# logmega.net
KiCad netlist of a schematic drawn in EAGLE
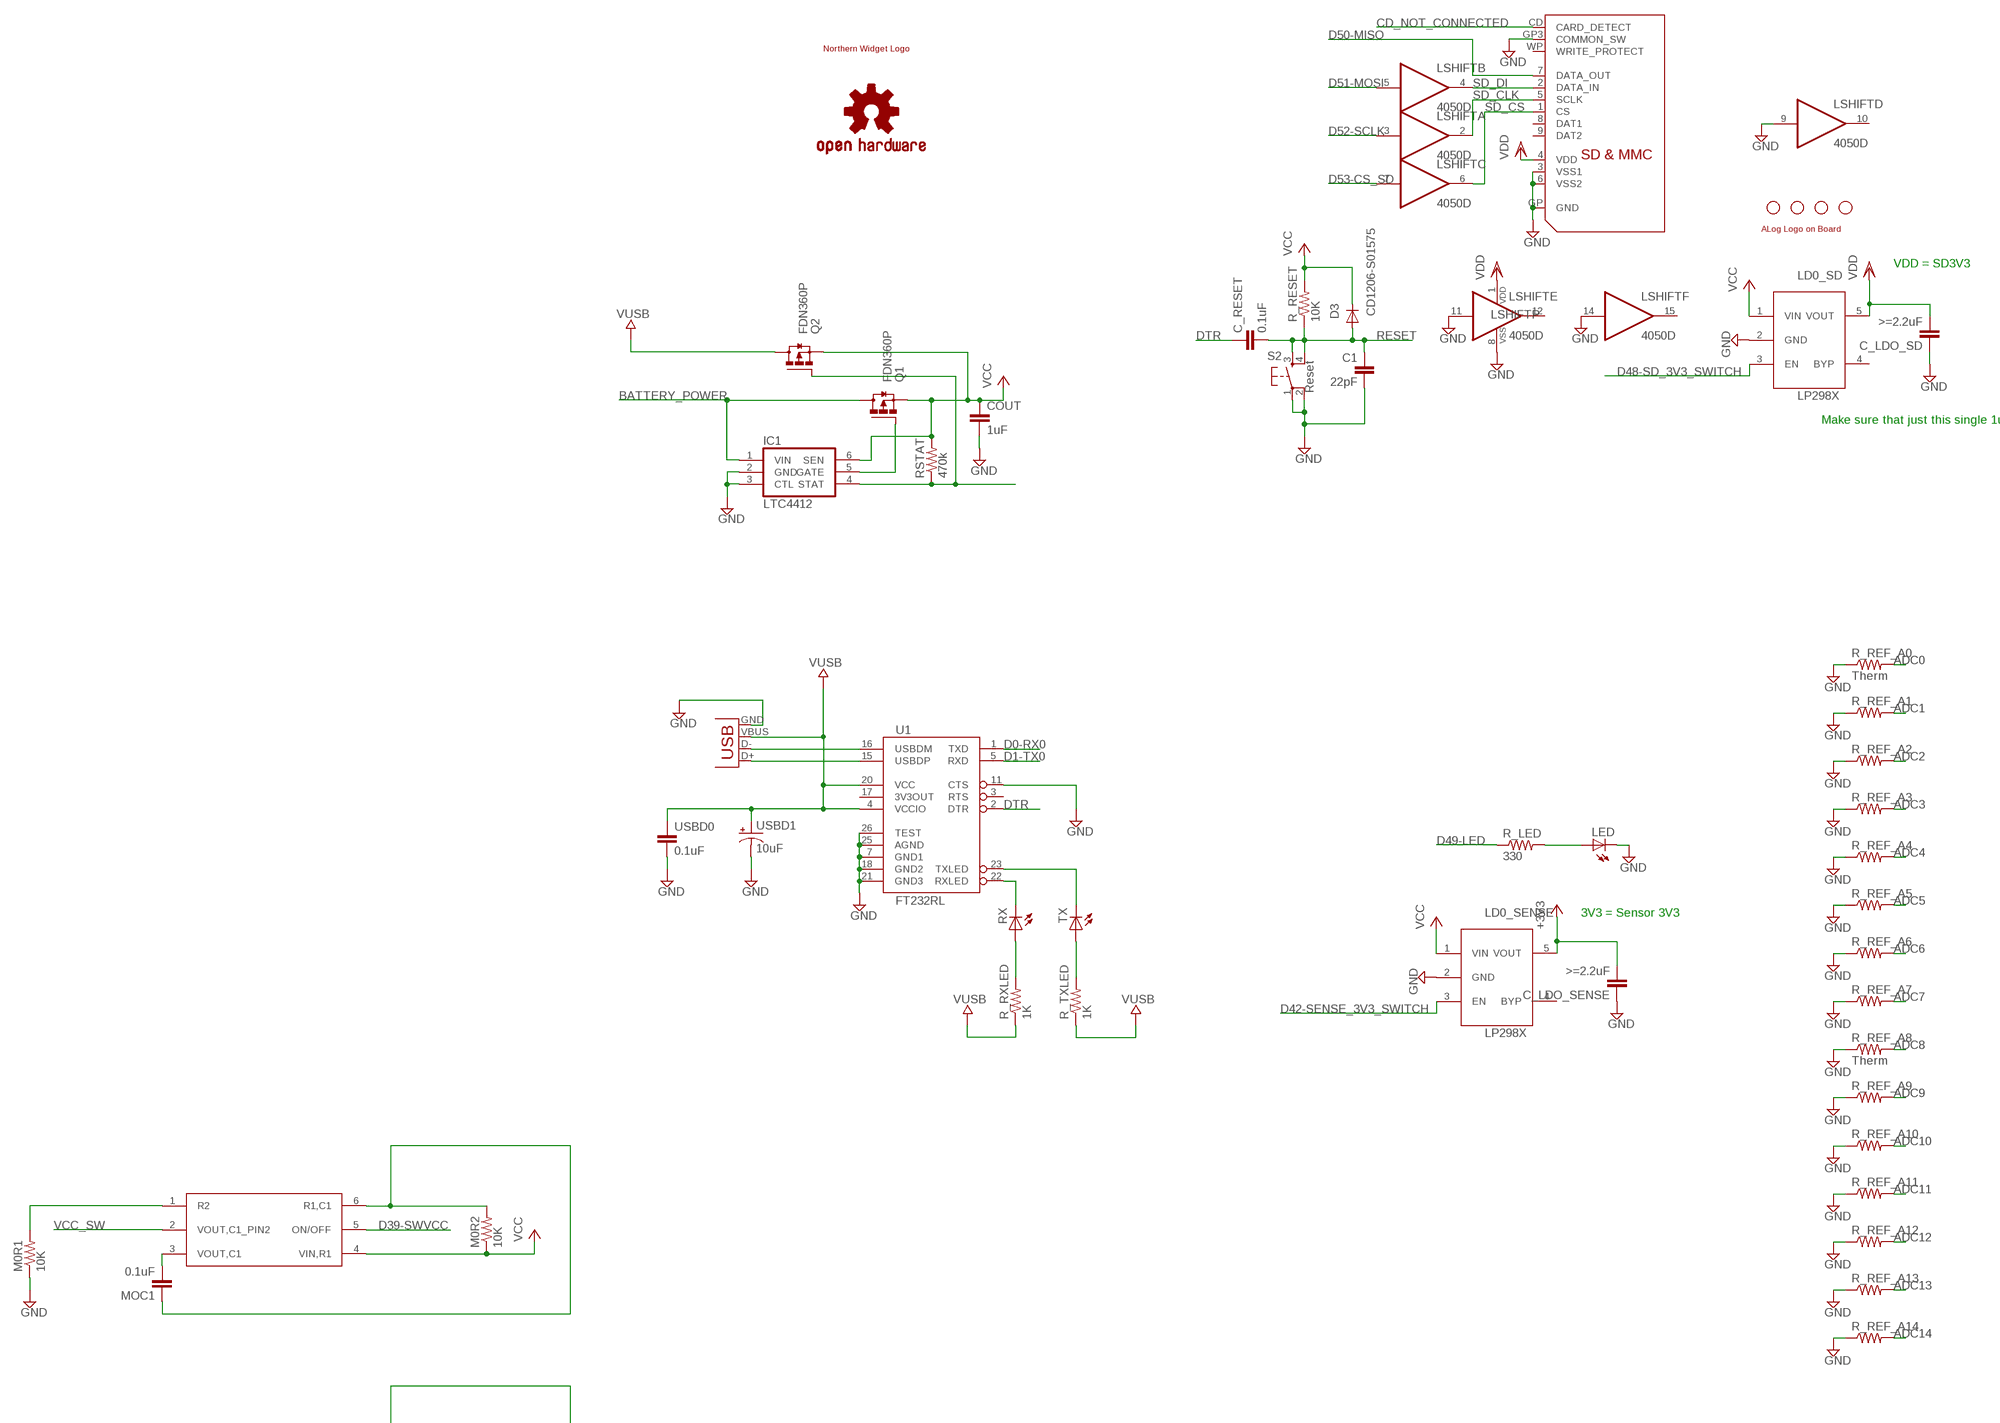
[diagram p0: schematic, sheet 1, part 1 of 3]
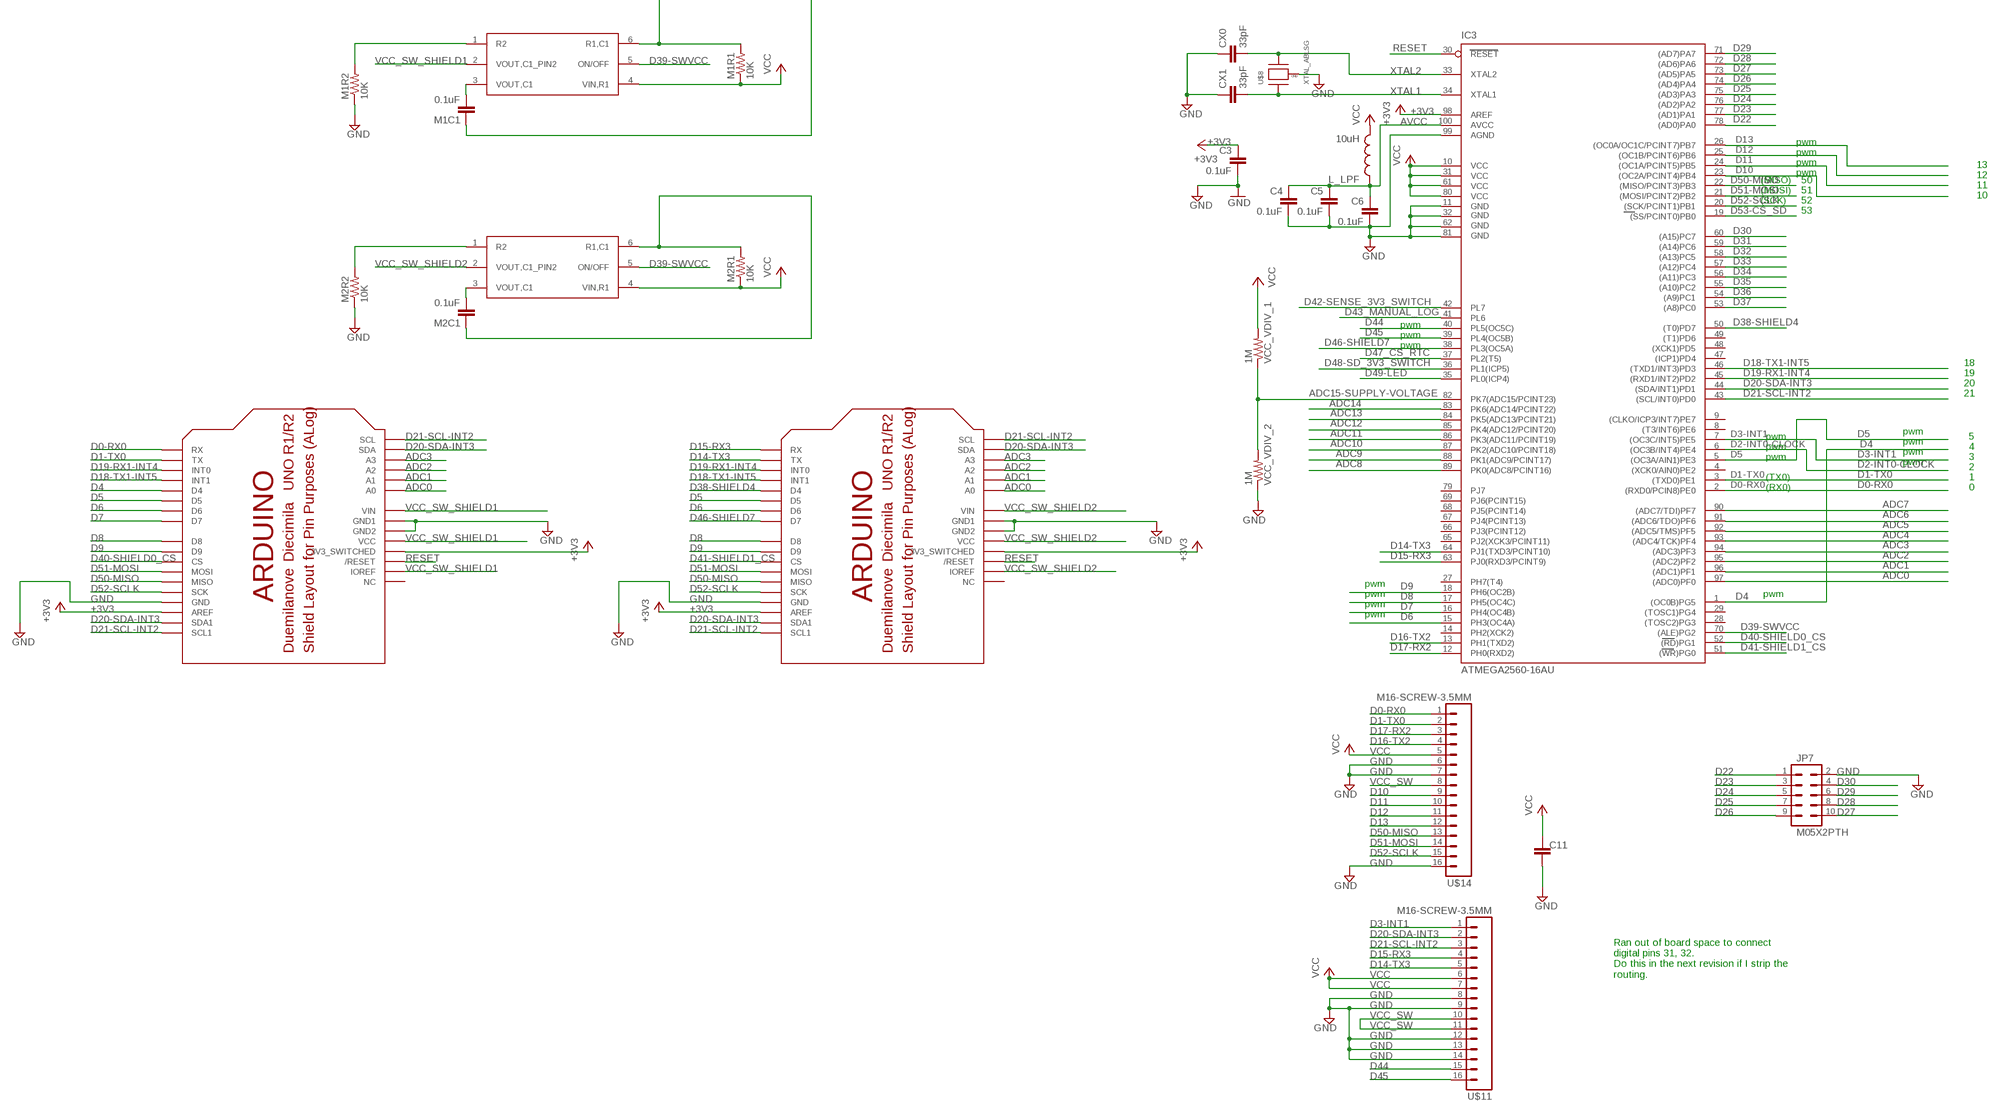
[diagram p1: schematic, sheet 1, part 2 of 3]
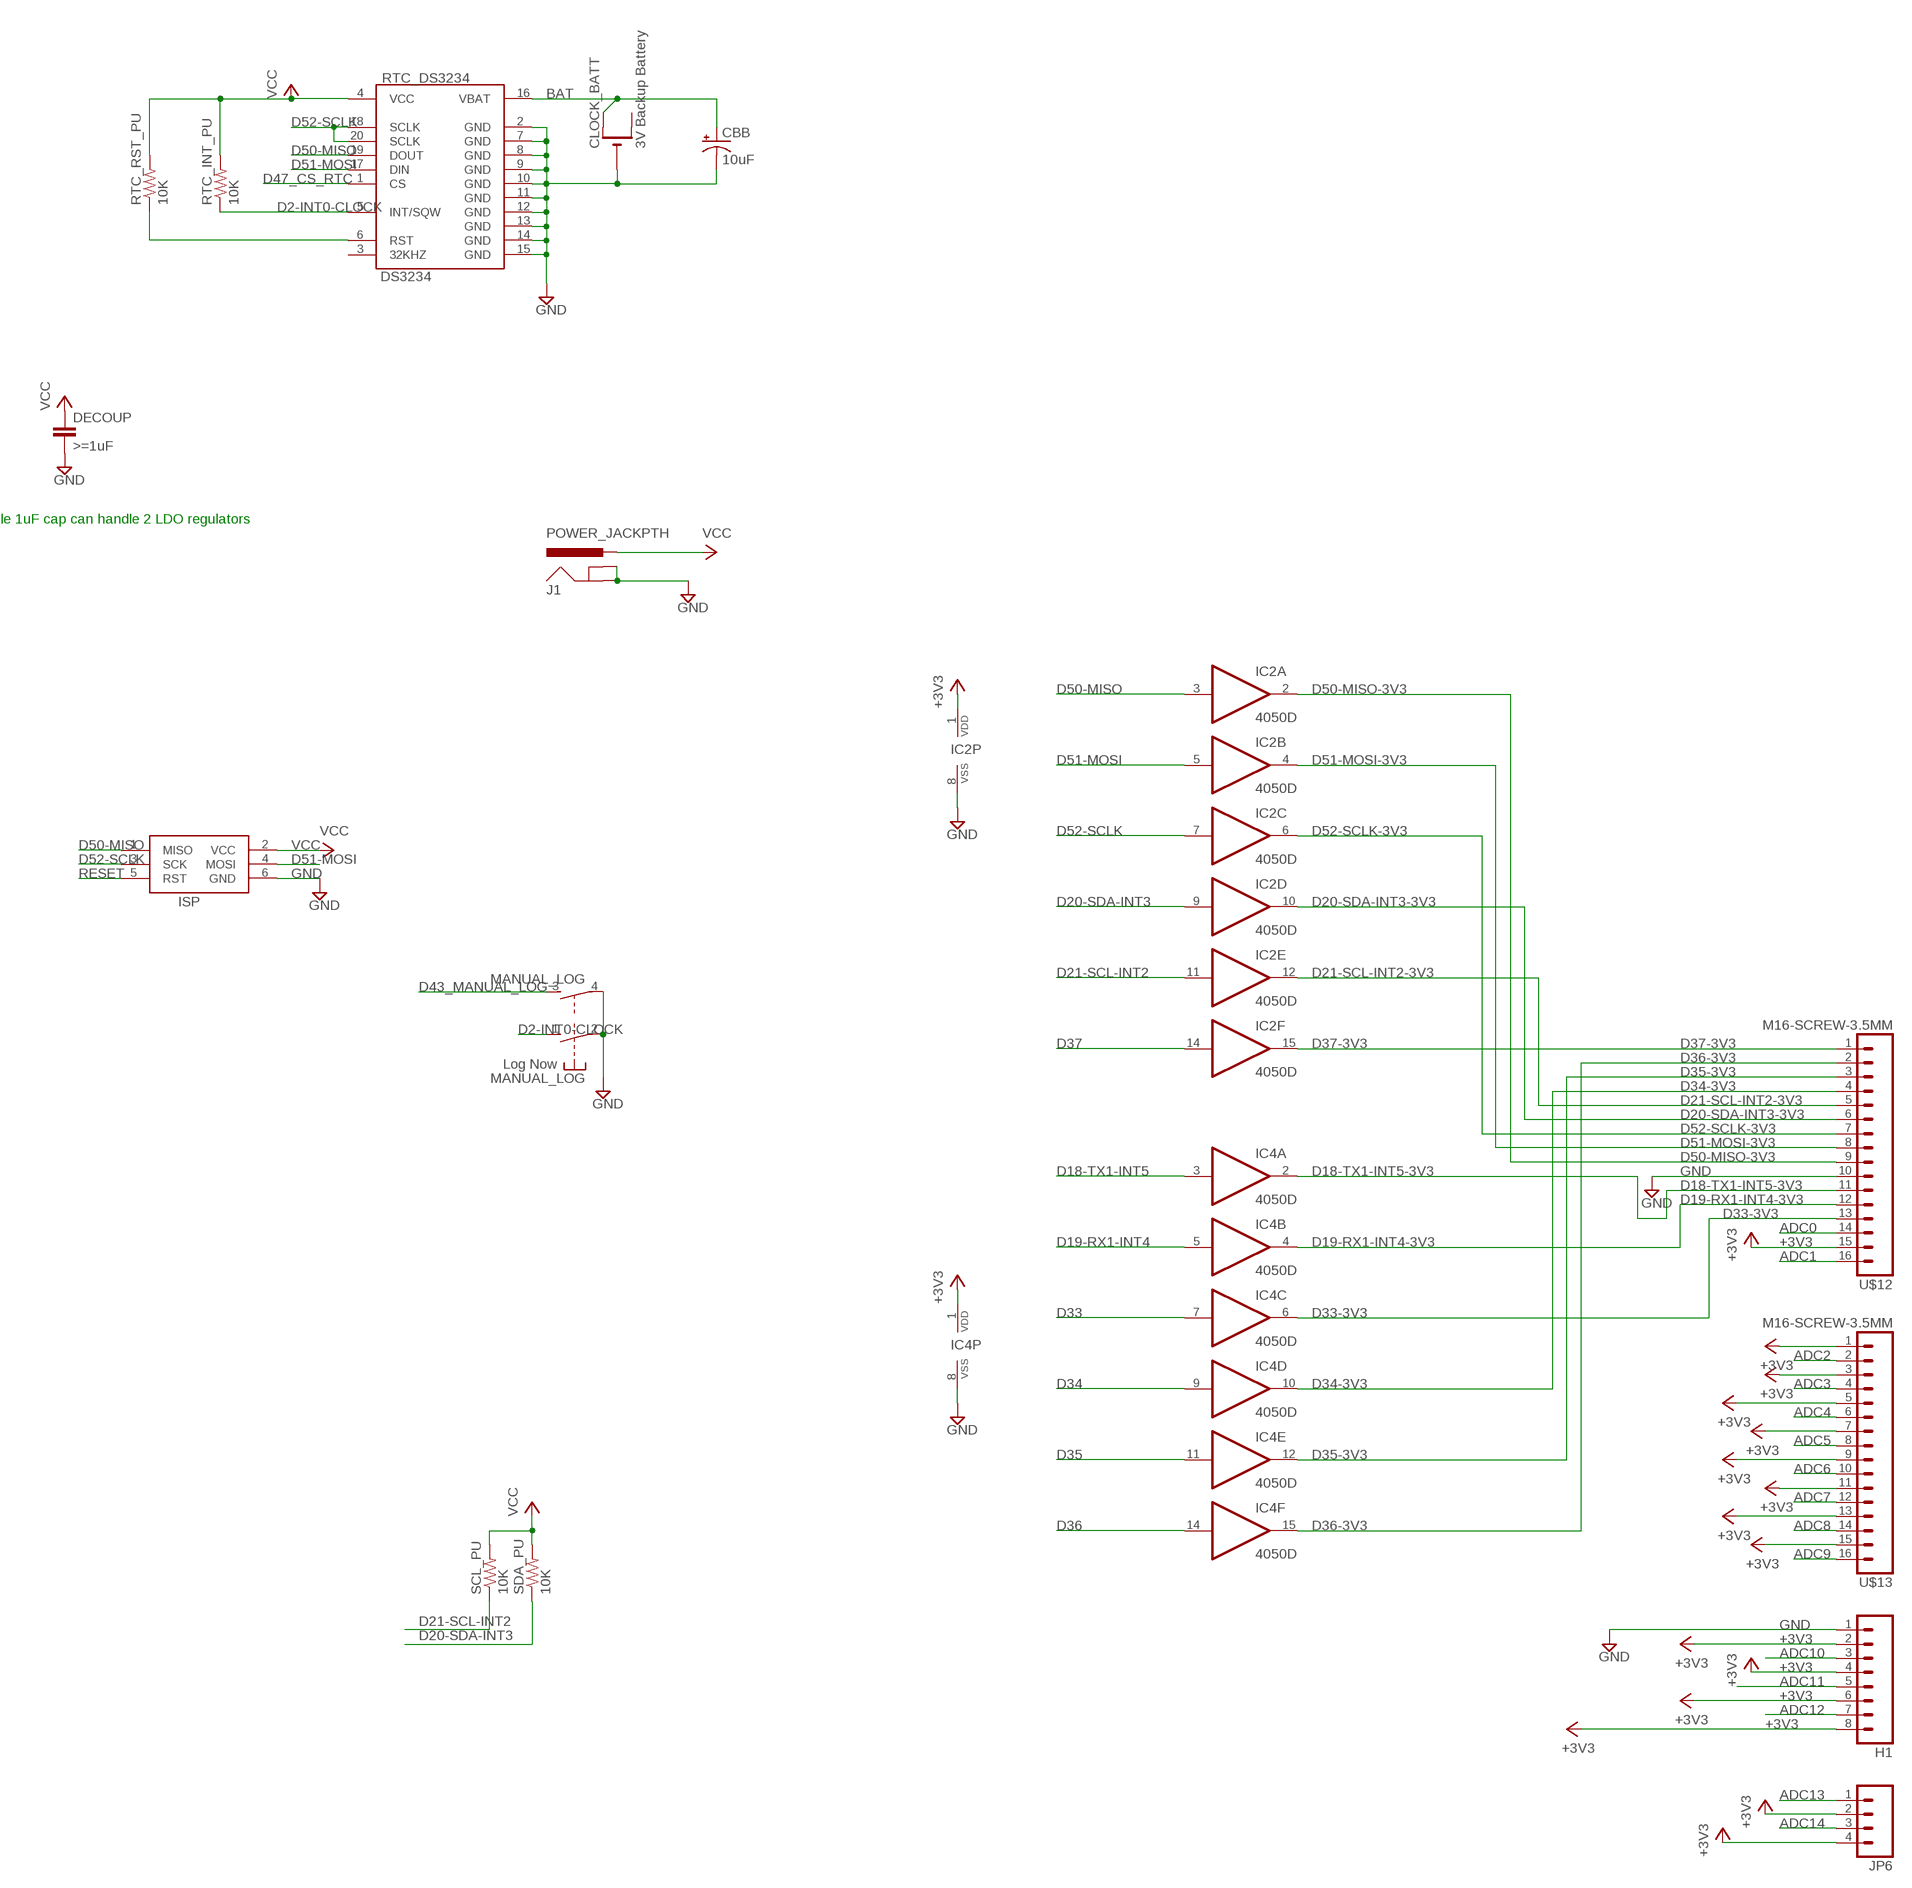
[diagram p2: schematic, sheet 1, part 3 of 3]

(export (version "E")
  (design (tool "Eeschema 10.0.6"))
  (components
    (comp (ref "C1")
      (value "22pF")
      (footprint "eagle-import:C0603-ROUND")
      (libsource (lib "eagle-import") (part "C-EU0603-RND"))
    )
    (comp (ref "C3")
      (value "0.1uF")
      (footprint "eagle-import:C0603-ROUND")
      (libsource (lib "eagle-import") (part "C-EU0603-RND"))
    )
    (comp (ref "C4")
      (value "0.1uF")
      (footprint "eagle-import:C0603-ROUND")
      (libsource (lib "eagle-import") (part "C-EU0603-RND"))
    )
    (comp (ref "C5")
      (value "0.1uF")
      (footprint "eagle-import:C0603-ROUND")
      (libsource (lib "eagle-import") (part "C-EU0603-RND"))
    )
    (comp (ref "C6")
      (value "0.1uF")
      (footprint "eagle-import:C0603-ROUND")
      (libsource (lib "eagle-import") (part "C-EU0603-RND"))
    )
    (comp (ref "C11")
      (value "0.1uF")
      (footprint "eagle-import:C0603-ROUND")
      (libsource (lib "eagle-import") (part "C-EU0603-RND"))
    )
    (comp (ref "CBB")
      (value "10uF")
      (footprint "eagle-import:EIA3216")
      (libsource (lib "eagle-import") (part "CAP_POL1206"))
    )
    (comp (ref "CLOCK_BATT")
      (value "3V Backup Battery")
      (footprint "eagle-import:CR2032-SMD")
      (libsource (lib "eagle-import") (part "CR2032"))
    )
    (comp (ref "COUT")
      (value "1uF")
      (footprint "eagle-import:C0603-ROUND")
      (libsource (lib "eagle-import") (part "C-EUC0603"))
    )
    (comp (ref "CX0")
      (value "33pF")
      (footprint "eagle-import:C0603")
      (libsource (lib "eagle-import") (part "resistor_C-EUC0603"))
    )
    (comp (ref "CX1")
      (value "33pF")
      (footprint "eagle-import:C0603")
      (libsource (lib "eagle-import") (part "resistor_C-EUC0603"))
    )
    (comp (ref "C_LDO_SD")
      (value ">=2.2uF")
      (footprint "eagle-import:C0603")
      (libsource (lib "eagle-import") (part "resistor_C-EUC0603"))
    )
    (comp (ref "C_LDO_SENSE")
      (value ">=2.2uF")
      (footprint "eagle-import:C0603")
      (libsource (lib "eagle-import") (part "resistor_C-EUC0603"))
    )
    (comp (ref "C_RESET")
      (value "0.1uF")
      (footprint "eagle-import:C0603")
      (libsource (lib "eagle-import") (part "resistor_C-EUC0603"))
    )
    (comp (ref "D3")
      (value "CD1206-S01575")
      (footprint "eagle-import:MINIMELF")
      (libsource (lib "eagle-import") (part "DIODE-MINIMELF"))
    )
    (comp (ref "DECOUP")
      (value ">=1uF")
      (footprint "eagle-import:C0603")
      (libsource (lib "eagle-import") (part "resistor_C-EUC0603"))
    )
    (comp (ref "H1")
      (value "M083.5MM-8")
      (footprint "eagle-import:SCREWTERMINAL-3.5MM-8")
      (libsource (lib "eagle-import") (part "M083.5MM-8"))
    )
    (comp (ref "IC1")
      (value "LTC4412")
      (footprint "eagle-import:TSOT23-6")
      (libsource (lib "eagle-import") (part "LTC4412S6E"))
    )
    (comp (ref "IC2")
      (value "4050D")
      (footprint "eagle-import:SO16")
      (libsource (lib "eagle-import") (part "4050D"))
    )
    (comp (ref "IC3")
      (value "ATMEGA2560-16AU")
      (footprint "eagle-import:TQFP100")
      (libsource (lib "eagle-import") (part "ATMEGA2560AU2560-16"))
    )
    (comp (ref "IC4")
      (value "4050D")
      (footprint "eagle-import:SO16")
      (libsource (lib "eagle-import") (part "4050D"))
    )
    (comp (ref "ISP")
      (value "AVRISP-6")
      (footprint "eagle-import:AVRISP")
      (libsource (lib "eagle-import") (part "AVRISP-6"))
    )
    (comp (ref "J1")
      (value "POWER_JACKPTH")
      (footprint "eagle-import:POWER_JACK_PTH")
      (libsource (lib "eagle-import") (part "POWER_JACKPTH"))
    )
    (comp (ref "JP1")
      (value "STAND-OFF")
      (footprint "eagle-import:STAND-OFF")
      (libsource (lib "eagle-import") (part "STAND-OFF"))
    )
    (comp (ref "JP2")
      (value "STAND-OFF")
      (footprint "eagle-import:STAND-OFF")
      (libsource (lib "eagle-import") (part "STAND-OFF"))
    )
    (comp (ref "JP3")
      (value "STAND-OFF")
      (footprint "eagle-import:STAND-OFF")
      (libsource (lib "eagle-import") (part "STAND-OFF"))
    )
    (comp (ref "JP4")
      (value "STAND-OFF")
      (footprint "eagle-import:STAND-OFF")
      (libsource (lib "eagle-import") (part "STAND-OFF"))
    )
    (comp (ref "JP5")
      (value "USB-B")
      (footprint "eagle-import:USB-B-PTH")
      (libsource (lib "eagle-import") (part "USBPTH"))
    )
    (comp (ref "JP6")
      (value "M04SCREW")
      (footprint "eagle-import:SCREWTERMINAL-3.5MM-4")
      (libsource (lib "eagle-import") (part "M04SCREW"))
    )
    (comp (ref "JP7")
      (value "M05X2PTH")
      (footprint "eagle-import:AVR_ICSP")
      (libsource (lib "eagle-import") (part "M05X2PTH"))
    )
    (comp (ref "LD0_SD")
      (value "LP2985")
      (footprint "eagle-import:SOT23-5L")
      (libsource (lib "eagle-import") (part "LP298XS"))
    )
    (comp (ref "LD0_SENSE")
      (value "LP2985")
      (footprint "eagle-import:SOT23-5L")
      (libsource (lib "eagle-import") (part "LP298XS"))
    )
    (comp (ref "LED")
      (value "LED3MM")
      (footprint "eagle-import:LED3MM")
      (libsource (lib "eagle-import") (part "LED3MM"))
    )
    (comp (ref "LOGO1")
      (value "OSHW-LOGOM")
      (footprint "eagle-import:OSHW-LOGO-M")
      (libsource (lib "eagle-import") (part "OSHW-LOGOM"))
    )
    (comp (ref "LSHIFT")
      (value "4050D")
      (footprint "eagle-import:SO16")
      (libsource (lib "eagle-import") (part "4050D"))
    )
    (comp (ref "L_LPF")
      (value "10uH")
      (footprint "eagle-import:0805")
      (libsource (lib "eagle-import") (part "INDUCTOR0805"))
    )
    (comp (ref "M0/SW")
      (value "FDG6342L")
      (footprint "eagle-import:SOT-363")
      (libsource (lib "eagle-import") (part "FDG6342L"))
    )
    (comp (ref "M0R1")
      (value "10K")
      (footprint "eagle-import:R0603")
      (libsource (lib "eagle-import") (part "R-US_R0603"))
    )
    (comp (ref "M0R2")
      (value "10K")
      (footprint "eagle-import:R0603")
      (libsource (lib "eagle-import") (part "R-US_R0603"))
    )
    (comp (ref "M1")
      (value "FDG6342L")
      (footprint "eagle-import:SOT-363")
      (libsource (lib "eagle-import") (part "FDG6342L"))
    )
    (comp (ref "M1C1")
      (value "0.1uF")
      (footprint "eagle-import:C0603")
      (libsource (lib "eagle-import") (part "resistor_C-EUC0603"))
    )
    (comp (ref "M1R1")
      (value "10K")
      (footprint "eagle-import:R0603")
      (libsource (lib "eagle-import") (part "R-US_R0603"))
    )
    (comp (ref "M1R2")
      (value "10K")
      (footprint "eagle-import:R0603")
      (libsource (lib "eagle-import") (part "R-US_R0603"))
    )
    (comp (ref "M2")
      (value "FDG6342L")
      (footprint "eagle-import:SOT-363")
      (libsource (lib "eagle-import") (part "FDG6342L"))
    )
    (comp (ref "M2C1")
      (value "0.1uF")
      (footprint "eagle-import:C0603")
      (libsource (lib "eagle-import") (part "resistor_C-EUC0603"))
    )
    (comp (ref "M2R1")
      (value "10K")
      (footprint "eagle-import:R0603")
      (libsource (lib "eagle-import") (part "R-US_R0603"))
    )
    (comp (ref "M2R2")
      (value "10K")
      (footprint "eagle-import:R0603")
      (libsource (lib "eagle-import") (part "R-US_R0603"))
    )
    (comp (ref "MANUAL_LOG")
      (value "Log Now")
      (footprint "eagle-import:PVA1F")
      (libsource (lib "eagle-import") (part "PVA1"))
    )
    (comp (ref "MOC1")
      (value "0.1uF")
      (footprint "eagle-import:C0603")
      (libsource (lib "eagle-import") (part "resistor_C-EUC0603"))
    )
    (comp (ref "Q1")
      (value "FDN360P")
      (footprint "eagle-import:SUPER-SOT3")
      (libsource (lib "eagle-import") (part "FDN360P"))
    )
    (comp (ref "Q2")
      (value "FDN360P")
      (footprint "eagle-import:SUPER-SOT3")
      (libsource (lib "eagle-import") (part "FDN360P"))
    )
    (comp (ref "RSTAT")
      (value "470k")
      (footprint "eagle-import:R0603")
      (libsource (lib "eagle-import") (part "R-US_R0603"))
    )
    (comp (ref "RTC_DS3234")
      (value "DS3234")
      (footprint "eagle-import:DS3234")
      (libsource (lib "eagle-import") (part "DS3234"))
    )
    (comp (ref "RTC_INT_PU")
      (value "10K")
      (footprint "eagle-import:R0603")
      (libsource (lib "eagle-import") (part "R-US_R0603"))
    )
    (comp (ref "RTC_RST_PU")
      (value "10K")
      (footprint "eagle-import:R0603")
      (libsource (lib "eagle-import") (part "R-US_R0603"))
    )
    (comp (ref "RX")
      (value "LED0603")
      (footprint "eagle-import:LED-0603")
      (libsource (lib "eagle-import") (part "SparkFun-LED_LED0603"))
    )
    (comp (ref "R_LED")
      (value "330")
      (footprint "eagle-import:R0603")
      (libsource (lib "eagle-import") (part "R-US_R0603"))
    )
    (comp (ref "R_REF_A0")
      (value "Therm")
      (footprint "eagle-import:0207_10")
      (libsource (lib "eagle-import") (part "resistor_R-US_0207/10"))
    )
    (comp (ref "R_REF_A1")
      (value "R-US_0207/10")
      (footprint "eagle-import:0207_10")
      (libsource (lib "eagle-import") (part "resistor_R-US_0207/10"))
    )
    (comp (ref "R_REF_A2")
      (value "R-US_0207/10")
      (footprint "eagle-import:0207_10")
      (libsource (lib "eagle-import") (part "resistor_R-US_0207/10"))
    )
    (comp (ref "R_REF_A3")
      (value "R-US_0207/10")
      (footprint "eagle-import:0207_10")
      (libsource (lib "eagle-import") (part "resistor_R-US_0207/10"))
    )
    (comp (ref "R_REF_A4")
      (value "R-US_0207/10")
      (footprint "eagle-import:0207_10")
      (libsource (lib "eagle-import") (part "resistor_R-US_0207/10"))
    )
    (comp (ref "R_REF_A5")
      (value "R-US_0207/10")
      (footprint "eagle-import:0207_10")
      (libsource (lib "eagle-import") (part "resistor_R-US_0207/10"))
    )
    (comp (ref "R_REF_A6")
      (value "R-US_0207/10")
      (footprint "eagle-import:0207_10")
      (libsource (lib "eagle-import") (part "resistor_R-US_0207/10"))
    )
    (comp (ref "R_REF_A7")
      (value "R-US_0207/10")
      (footprint "eagle-import:0207_10")
      (libsource (lib "eagle-import") (part "resistor_R-US_0207/10"))
    )
    (comp (ref "R_REF_A8")
      (value "Therm")
      (footprint "eagle-import:0207_10")
      (libsource (lib "eagle-import") (part "resistor_R-US_0207/10"))
    )
    (comp (ref "R_REF_A9")
      (value "R-US_0207/10")
      (footprint "eagle-import:0207_10")
      (libsource (lib "eagle-import") (part "resistor_R-US_0207/10"))
    )
    (comp (ref "R_REF_A10")
      (value "R-US_0207/10")
      (footprint "eagle-import:0207_10")
      (libsource (lib "eagle-import") (part "resistor_R-US_0207/10"))
    )
    (comp (ref "R_REF_A11")
      (value "R-US_0207/10")
      (footprint "eagle-import:0207_10")
      (libsource (lib "eagle-import") (part "resistor_R-US_0207/10"))
    )
    (comp (ref "R_REF_A12")
      (value "R-US_0207/10")
      (footprint "eagle-import:0207_10")
      (libsource (lib "eagle-import") (part "resistor_R-US_0207/10"))
    )
    (comp (ref "R_REF_A13")
      (value "R-US_0207/10")
      (footprint "eagle-import:0207_10")
      (libsource (lib "eagle-import") (part "resistor_R-US_0207/10"))
    )
    (comp (ref "R_REF_A14")
      (value "R-US_0207/10")
      (footprint "eagle-import:0207_10")
      (libsource (lib "eagle-import") (part "resistor_R-US_0207/10"))
    )
    (comp (ref "R_RESET")
      (value "10K")
      (footprint "eagle-import:R0603")
      (libsource (lib "eagle-import") (part "R-US_R0603"))
    )
    (comp (ref "R_RXLED")
      (value "1K")
      (footprint "eagle-import:R0603")
      (libsource (lib "eagle-import") (part "R-US_R0603"))
    )
    (comp (ref "R_TXLED")
      (value "1K")
      (footprint "eagle-import:R0603")
      (libsource (lib "eagle-import") (part "R-US_R0603"))
    )
    (comp (ref "S2")
      (value "Reset")
      (footprint "eagle-import:TACTILE-PTH")
      (libsource (lib "eagle-import") (part "TAC_SWITCHPTH"))
    )
    (comp (ref "SCL_PU")
      (value "10K")
      (footprint "eagle-import:R0603")
      (libsource (lib "eagle-import") (part "R-US_R0603"))
    )
    (comp (ref "SD")
      (value "SDMMC06132")
      (footprint "eagle-import:06132")
      (libsource (lib "eagle-import") (part "SDMMC06132"))
    )
    (comp (ref "SDA_PU")
      (value "10K")
      (footprint "eagle-import:R0603")
      (libsource (lib "eagle-import") (part "R-US_R0603"))
    )
    (comp (ref "TX")
      (value "LED0603")
      (footprint "eagle-import:LED-0603")
      (libsource (lib "eagle-import") (part "SparkFun-LED_LED0603"))
    )
    (comp (ref "U$1")
      (value "NWLOGO")
      (footprint "eagle-import:NWLOGO")
      (libsource (lib "eagle-import") (part "NWLOGO"))
    )
    (comp (ref "U$2")
      (value "ALOG_LOGO_V1_5.5MM")
      (footprint "eagle-import:ALOG_LOGO_V1_SMALL")
      (libsource (lib "eagle-import") (part "ALOG_LOGO_V1_5.5MM"))
    )
    (comp (ref "U$7")
      (value "ARDUINO_SHIELD_BIGLOG_2")
      (footprint "eagle-import:ARDUINO_SHIELD_PO_BL2")
      (libsource (lib "eagle-import") (part "ARDUINO_SHIELD_BIGLOG_2"))
    )
    (comp (ref "U$8")
      (value "XTAL_ABLSG")
      (footprint "eagle-import:AT49")
      (libsource (lib "eagle-import") (part "XTAL_ABLSG"))
    )
    (comp (ref "U$9")
      (value "ARDUINO_SHIELD_BIGLOG_1")
      (footprint "eagle-import:ARDUINO_SHIELD_PO_BL1")
      (libsource (lib "eagle-import") (part "ARDUINO_SHIELD_BIGLOG_1"))
    )
    (comp (ref "U$11")
      (value "M16-SCREW-3.5MM")
      (footprint "eagle-import:M16-SCREW-3.5MM")
      (libsource (lib "eagle-import") (part "M16-SCREW-3.5MM"))
    )
    (comp (ref "U$12")
      (value "M16-SCREW-3.5MM")
      (footprint "eagle-import:M16-SCREW-3.5MM")
      (libsource (lib "eagle-import") (part "M16-SCREW-3.5MM"))
    )
    (comp (ref "U$13")
      (value "M16-SCREW-3.5MM")
      (footprint "eagle-import:M16-SCREW-3.5MM")
      (libsource (lib "eagle-import") (part "M16-SCREW-3.5MM"))
    )
    (comp (ref "U$14")
      (value "M16-SCREW-3.5MM")
      (footprint "eagle-import:M16-SCREW-3.5MM")
      (libsource (lib "eagle-import") (part "M16-SCREW-3.5MM"))
    )
    (comp (ref "U1")
      (value "FT232RL")
      (footprint "eagle-import:SSOP28DB")
      (libsource (lib "eagle-import") (part "FT232RL-BASICSSOP"))
    )
    (comp (ref "USBD0")
      (value "0.1uF")
      (footprint "eagle-import:C0603")
      (libsource (lib "eagle-import") (part "resistor_C-EUC0603"))
    )
    (comp (ref "USBD1")
      (value "10uF")
      (footprint "eagle-import:EIA3216")
      (libsource (lib "eagle-import") (part "CAP_POL1206"))
    )
    (comp (ref "VCC_VDIV_1")
      (value "1M")
      (footprint "eagle-import:R0603")
      (libsource (lib "eagle-import") (part "R-US_R0603"))
    )
    (comp (ref "VCC_VDIV_2")
      (value "1M")
      (footprint "eagle-import:R0603")
      (libsource (lib "eagle-import") (part "R-US_R0603"))
    )
  )
  (nets
    (net (code "1") (name "+3V3") (class "Default")
      (node (ref "C3") (pin "1") (pinfunction "1_1") (pintype "passive"))
      (node (ref "C_LDO_SENSE") (pin "2") (pinfunction "2_2") (pintype "passive"))
      (node (ref "H1") (pin "2") (pinfunction "2_2") (pintype "passive"))
      (node (ref "H1") (pin "4") (pinfunction "4_4") (pintype "passive"))
      (node (ref "H1") (pin "6") (pinfunction "6_6") (pintype "passive"))
      (node (ref "H1") (pin "8") (pinfunction "8_8") (pintype "passive"))
      (node (ref "IC2") (pin "1") (pinfunction "VDD_1") (pintype "power_in"))
      (node (ref "IC3") (pin "98") (pinfunction "AREF_98") (pintype "bidirectional"))
      (node (ref "IC4") (pin "1") (pinfunction "VDD_1") (pintype "power_in"))
      (node (ref "JP6") (pin "2") (pinfunction "2_2") (pintype "passive"))
      (node (ref "JP6") (pin "4") (pinfunction "4_4") (pintype "passive"))
      (node (ref "LD0_SENSE") (pin "5") (pinfunction "VOUT_5") (pintype "bidirectional"))
      (node (ref "U$12") (pin "15") (pinfunction "15_15") (pintype "passive"))
      (node (ref "U$13") (pin "1") (pinfunction "1_1") (pintype "passive"))
      (node (ref "U$13") (pin "11") (pinfunction "11_11") (pintype "passive"))
      (node (ref "U$13") (pin "13") (pinfunction "13_13") (pintype "passive"))
      (node (ref "U$13") (pin "15") (pinfunction "15_15") (pintype "passive"))
      (node (ref "U$13") (pin "3") (pinfunction "3_3") (pintype "passive"))
      (node (ref "U$13") (pin "5") (pinfunction "5_5") (pintype "passive"))
      (node (ref "U$13") (pin "7") (pinfunction "7_7") (pintype "passive"))
      (node (ref "U$13") (pin "9") (pinfunction "9_9") (pintype "passive"))
      (node (ref "U$7") (pin "3.3V") (pinfunction "3V3_SWITCHED_3.3V") (pintype "power_in"))
      (node (ref "U$7") (pin "AREF") (pinfunction "AREF_AREF") (pintype "bidirectional"))
      (node (ref "U$9") (pin "3.3V") (pinfunction "3V3_SWITCHED_3.3V") (pintype "power_in"))
      (node (ref "U$9") (pin "AREF") (pinfunction "AREF_AREF") (pintype "bidirectional"))
    )
    (net (code "2") (name "/ADC0") (class "Default")
      (node (ref "IC3") (pin "97") (pinfunction "(ADC0)PF0_97") (pintype "bidirectional"))
      (node (ref "R_REF_A0") (pin "2") (pinfunction "2_2") (pintype "passive"))
      (node (ref "U$12") (pin "14") (pinfunction "14_14") (pintype "passive"))
      (node (ref "U$7") (pin "A0") (pinfunction "A0_A0") (pintype "bidirectional"))
      (node (ref "U$9") (pin "A0") (pinfunction "A0_A0") (pintype "bidirectional"))
    )
    (net (code "3") (name "/ADC1") (class "Default")
      (node (ref "IC3") (pin "96") (pinfunction "(ADC1)PF1_96") (pintype "bidirectional"))
      (node (ref "R_REF_A1") (pin "2") (pinfunction "2_2") (pintype "passive"))
      (node (ref "U$12") (pin "16") (pinfunction "16_16") (pintype "passive"))
      (node (ref "U$7") (pin "A1") (pinfunction "A1_A1") (pintype "bidirectional"))
      (node (ref "U$9") (pin "A1") (pinfunction "A1_A1") (pintype "bidirectional"))
    )
    (net (code "4") (name "/ADC2") (class "Default")
      (node (ref "IC3") (pin "95") (pinfunction "(ADC2)PF2_95") (pintype "bidirectional"))
      (node (ref "R_REF_A2") (pin "2") (pinfunction "2_2") (pintype "passive"))
      (node (ref "U$13") (pin "2") (pinfunction "2_2") (pintype "passive"))
      (node (ref "U$7") (pin "A2") (pinfunction "A2_A2") (pintype "bidirectional"))
      (node (ref "U$9") (pin "A2") (pinfunction "A2_A2") (pintype "bidirectional"))
    )
    (net (code "5") (name "/ADC3") (class "Default")
      (node (ref "IC3") (pin "94") (pinfunction "(ADC3)PF3_94") (pintype "bidirectional"))
      (node (ref "R_REF_A3") (pin "2") (pinfunction "2_2") (pintype "passive"))
      (node (ref "U$13") (pin "4") (pinfunction "4_4") (pintype "passive"))
      (node (ref "U$7") (pin "A3") (pinfunction "A3_A3") (pintype "bidirectional"))
      (node (ref "U$9") (pin "A3") (pinfunction "A3_A3") (pintype "bidirectional"))
    )
    (net (code "6") (name "/ADC4") (class "Default")
      (node (ref "IC3") (pin "93") (pinfunction "(ADC4/TCK)PF4_93") (pintype "bidirectional"))
      (node (ref "R_REF_A4") (pin "2") (pinfunction "2_2") (pintype "passive"))
      (node (ref "U$13") (pin "6") (pinfunction "6_6") (pintype "passive"))
    )
    (net (code "7") (name "/ADC5") (class "Default")
      (node (ref "IC3") (pin "92") (pinfunction "(ADC5/TMS)PF5_92") (pintype "bidirectional"))
      (node (ref "R_REF_A5") (pin "2") (pinfunction "2_2") (pintype "passive"))
      (node (ref "U$13") (pin "8") (pinfunction "8_8") (pintype "passive"))
    )
    (net (code "8") (name "/ADC6") (class "Default")
      (node (ref "IC3") (pin "91") (pinfunction "(ADC6/TDO)PF6_91") (pintype "bidirectional"))
      (node (ref "R_REF_A6") (pin "2") (pinfunction "2_2") (pintype "passive"))
      (node (ref "U$13") (pin "10") (pinfunction "10_10") (pintype "passive"))
    )
    (net (code "9") (name "/ADC7") (class "Default")
      (node (ref "IC3") (pin "90") (pinfunction "(ADC7/TDI)PF7_90") (pintype "bidirectional"))
      (node (ref "R_REF_A7") (pin "2") (pinfunction "2_2") (pintype "passive"))
      (node (ref "U$13") (pin "12") (pinfunction "12_12") (pintype "passive"))
    )
    (net (code "10") (name "/ADC8") (class "Default")
      (node (ref "IC3") (pin "89") (pinfunction "PK0(ADC8/PCINT16)_89") (pintype "bidirectional"))
      (node (ref "R_REF_A8") (pin "2") (pinfunction "2_2") (pintype "passive"))
      (node (ref "U$13") (pin "14") (pinfunction "14_14") (pintype "passive"))
    )
    (net (code "11") (name "/ADC9") (class "Default")
      (node (ref "IC3") (pin "88") (pinfunction "PK1(ADC9/PCINT17)_88") (pintype "bidirectional"))
      (node (ref "R_REF_A9") (pin "2") (pinfunction "2_2") (pintype "passive"))
      (node (ref "U$13") (pin "16") (pinfunction "16_16") (pintype "passive"))
    )
    (net (code "12") (name "/ADC10") (class "Default")
      (node (ref "H1") (pin "3") (pinfunction "3_3") (pintype "passive"))
      (node (ref "IC3") (pin "87") (pinfunction "PK2(ADC10/PCINT18)_87") (pintype "bidirectional"))
      (node (ref "R_REF_A10") (pin "2") (pinfunction "2_2") (pintype "passive"))
    )
    (net (code "13") (name "/ADC11") (class "Default")
      (node (ref "H1") (pin "5") (pinfunction "5_5") (pintype "passive"))
      (node (ref "IC3") (pin "86") (pinfunction "PK3(ADC11/PCINT19)_86") (pintype "bidirectional"))
      (node (ref "R_REF_A11") (pin "2") (pinfunction "2_2") (pintype "passive"))
    )
    (net (code "14") (name "/ADC12") (class "Default")
      (node (ref "H1") (pin "7") (pinfunction "7_7") (pintype "passive"))
      (node (ref "IC3") (pin "85") (pinfunction "PK4(ADC12/PCINT20)_85") (pintype "bidirectional"))
      (node (ref "R_REF_A12") (pin "2") (pinfunction "2_2") (pintype "passive"))
    )
    (net (code "15") (name "/ADC13") (class "Default")
      (node (ref "IC3") (pin "84") (pinfunction "PK5(ADC13/PCINT21)_84") (pintype "bidirectional"))
      (node (ref "JP6") (pin "1") (pinfunction "1_1") (pintype "passive"))
      (node (ref "R_REF_A13") (pin "2") (pinfunction "2_2") (pintype "passive"))
    )
    (net (code "16") (name "/ADC14") (class "Default")
      (node (ref "IC3") (pin "83") (pinfunction "PK6(ADC14/PCINT22)_83") (pintype "bidirectional"))
      (node (ref "JP6") (pin "3") (pinfunction "3_3") (pintype "passive"))
      (node (ref "R_REF_A14") (pin "2") (pinfunction "2_2") (pintype "passive"))
    )
    (net (code "17") (name "/ADC15-SUPPLY-VOLTAGE") (class "Default")
      (node (ref "IC3") (pin "82") (pinfunction "PK7(ADC15/PCINT23)_82") (pintype "bidirectional"))
      (node (ref "VCC_VDIV_1") (pin "1") (pinfunction "1_1") (pintype "passive"))
      (node (ref "VCC_VDIV_2") (pin "2") (pinfunction "2_2") (pintype "passive"))
    )
    (net (code "18") (name "/AVCC") (class "Default")
      (node (ref "C4") (pin "1") (pinfunction "1_1") (pintype "passive"))
      (node (ref "C5") (pin "1") (pinfunction "1_1") (pintype "passive"))
      (node (ref "C6") (pin "1") (pinfunction "1_1") (pintype "passive"))
      (node (ref "IC3") (pin "100") (pinfunction "AVCC_100") (pintype "power_in"))
      (node (ref "L_LPF") (pin "1") (pinfunction "1_1") (pintype "passive"))
    )
    (net (code "19") (name "/BAT") (class "Default")
      (node (ref "CBB") (pin "A") (pinfunction "+_A") (pintype "passive"))
      (node (ref "CLOCK_BATT") (pin "+$1") (pinfunction "+_+$1") (pintype "passive"))
      (node (ref "RTC_DS3234") (pin "16") (pinfunction "VBAT_16") (pintype "bidirectional"))
    )
    (net (code "20") (name "/BATTERY_POWER") (class "Default")
      (node (ref "IC1") (pin "1") (pinfunction "VIN_1") (pintype "input"))
      (node (ref "Q1") (pin "3") (pinfunction "D_3") (pintype "passive"))
    )
    (net (code "21") (name "/CD_NOT_CONNECTED") (class "Default")
      (node (ref "SD") (pin "CD") (pinfunction "CARD_DETECT_CD") (pintype "passive"))
    )
    (net (code "22") (name "/D0-RX0") (class "Default")
      (node (ref "IC3") (pin "2") (pinfunction "(RXD0/PCIN8)PE0_2") (pintype "bidirectional"))
      (node (ref "U$14") (pin "1") (pinfunction "1_1") (pintype "passive"))
      (node (ref "U$9") (pin "RX") (pinfunction "RX_RX") (pintype "bidirectional"))
      (node (ref "U1") (pin "1") (pinfunction "TXD_1") (pintype "output"))
    )
    (net (code "23") (name "/D1-TX0") (class "Default")
      (node (ref "IC3") (pin "3") (pinfunction "(TXD0)PE1_3") (pintype "bidirectional"))
      (node (ref "U$14") (pin "2") (pinfunction "2_2") (pintype "passive"))
      (node (ref "U$9") (pin "TX") (pinfunction "TX_TX") (pintype "bidirectional"))
      (node (ref "U1") (pin "5") (pinfunction "RXD_5") (pintype "input"))
    )
    (net (code "24") (name "/D2-INT0-CLOCK") (class "Default")
      (node (ref "IC3") (pin "6") (pinfunction "(OC3B/INT4)PE4_6") (pintype "bidirectional"))
      (node (ref "MANUAL_LOG") (pin "1") (pinfunction "S_1") (pintype "passive"))
      (node (ref "RTC_DS3234") (pin "5") (pinfunction "INT/SQW_5") (pintype "bidirectional"))
      (node (ref "RTC_INT_PU") (pin "1") (pinfunction "1_1") (pintype "passive"))
    )
    (net (code "25") (name "/D3-INT1") (class "Default")
      (node (ref "IC3") (pin "7") (pinfunction "(OC3C/INT5)PE5_7") (pintype "bidirectional"))
      (node (ref "U$11") (pin "1") (pinfunction "1_1") (pintype "passive"))
    )
    (net (code "26") (name "/D4") (class "Default")
      (node (ref "IC3") (pin "1") (pinfunction "(OC0B)PG5_1") (pintype "bidirectional"))
      (node (ref "U$9") (pin "D4") (pinfunction "D4_D4") (pintype "bidirectional"))
    )
    (net (code "27") (name "/D5") (class "Default")
      (node (ref "IC3") (pin "5") (pinfunction "(OC3A/AIN1)PE3_5") (pintype "bidirectional"))
      (node (ref "U$7") (pin "D5") (pinfunction "D5_D5") (pintype "bidirectional"))
      (node (ref "U$9") (pin "D5") (pinfunction "D5_D5") (pintype "bidirectional"))
    )
    (net (code "28") (name "/D6") (class "Default")
      (node (ref "IC3") (pin "15") (pinfunction "PH3(OC4A)_15") (pintype "bidirectional"))
      (node (ref "U$7") (pin "D6") (pinfunction "D6_D6") (pintype "bidirectional"))
      (node (ref "U$9") (pin "D6") (pinfunction "D6_D6") (pintype "bidirectional"))
    )
    (net (code "29") (name "/D7") (class "Default")
      (node (ref "IC3") (pin "16") (pinfunction "PH4(OC4B)_16") (pintype "bidirectional"))
      (node (ref "U$9") (pin "D7") (pinfunction "D7_D7") (pintype "bidirectional"))
    )
    (net (code "30") (name "/D8") (class "Default")
      (node (ref "IC3") (pin "17") (pinfunction "PH5(OC4C)_17") (pintype "bidirectional"))
      (node (ref "U$7") (pin "D8") (pinfunction "D8_D8") (pintype "bidirectional"))
      (node (ref "U$9") (pin "D8") (pinfunction "D8_D8") (pintype "bidirectional"))
    )
    (net (code "31") (name "/D9") (class "Default")
      (node (ref "IC3") (pin "18") (pinfunction "PH6(OC2B)_18") (pintype "bidirectional"))
      (node (ref "U$7") (pin "D9") (pinfunction "D9_D9") (pintype "bidirectional"))
      (node (ref "U$9") (pin "D9") (pinfunction "D9_D9") (pintype "bidirectional"))
    )
    (net (code "32") (name "/D10") (class "Default")
      (node (ref "IC3") (pin "23") (pinfunction "(OC2A/PCINT4)PB4_23") (pintype "bidirectional"))
      (node (ref "U$14") (pin "9") (pinfunction "9_9") (pintype "passive"))
    )
    (net (code "33") (name "/D11") (class "Default")
      (node (ref "IC3") (pin "24") (pinfunction "(OC1A/PCINT5)PB5_24") (pintype "bidirectional"))
      (node (ref "U$14") (pin "10") (pinfunction "10_10") (pintype "passive"))
    )
    (net (code "34") (name "/D12") (class "Default")
      (node (ref "IC3") (pin "25") (pinfunction "(OC1B/PCINT6)PB6_25") (pintype "bidirectional"))
      (node (ref "U$14") (pin "11") (pinfunction "11_11") (pintype "passive"))
    )
    (net (code "35") (name "/D13") (class "Default")
      (node (ref "IC3") (pin "26") (pinfunction "(OC0A/OC1C/PCINT7)PB7_26") (pintype "bidirectional"))
      (node (ref "U$14") (pin "12") (pinfunction "12_12") (pintype "passive"))
    )
    (net (code "36") (name "/D14-TX3") (class "Default")
      (node (ref "IC3") (pin "64") (pinfunction "PJ1(TXD3/PCINT10)_64") (pintype "bidirectional"))
      (node (ref "U$11") (pin "5") (pinfunction "5_5") (pintype "passive"))
      (node (ref "U$7") (pin "TX") (pinfunction "TX_TX") (pintype "bidirectional"))
    )
    (net (code "37") (name "/D15-RX3") (class "Default")
      (node (ref "IC3") (pin "63") (pinfunction "PJ0(RXD3/PCINT9)_63") (pintype "bidirectional"))
      (node (ref "U$11") (pin "4") (pinfunction "4_4") (pintype "passive"))
      (node (ref "U$7") (pin "RX") (pinfunction "RX_RX") (pintype "bidirectional"))
    )
    (net (code "38") (name "/D16-TX2") (class "Default")
      (node (ref "IC3") (pin "13") (pinfunction "PH1(TXD2)_13") (pintype "bidirectional"))
      (node (ref "U$14") (pin "4") (pinfunction "4_4") (pintype "passive"))
    )
    (net (code "39") (name "/D17-RX2") (class "Default")
      (node (ref "IC3") (pin "12") (pinfunction "PH0(RXD2)_12") (pintype "bidirectional"))
      (node (ref "U$14") (pin "3") (pinfunction "3_3") (pintype "passive"))
    )
    (net (code "40") (name "/D18-TX1-INT5") (class "Default")
      (node (ref "IC3") (pin "46") (pinfunction "(TXD1/INT3)PD3_46") (pintype "bidirectional"))
      (node (ref "IC4") (pin "3") (pinfunction "I_3") (pintype "input"))
      (node (ref "U$7") (pin "D3") (pinfunction "INT1_D3") (pintype "bidirectional"))
      (node (ref "U$9") (pin "D3") (pinfunction "INT1_D3") (pintype "bidirectional"))
    )
    (net (code "41") (name "/D18-TX1-INT5-3V3") (class "Default")
      (node (ref "IC4") (pin "2") (pinfunction "O_2") (pintype "output"))
      (node (ref "U$12") (pin "11") (pinfunction "11_11") (pintype "passive"))
    )
    (net (code "42") (name "/D19-RX1-INT4") (class "Default")
      (node (ref "IC3") (pin "45") (pinfunction "(RXD1/INT2)PD2_45") (pintype "bidirectional"))
      (node (ref "IC4") (pin "5") (pinfunction "I_5") (pintype "input"))
      (node (ref "U$7") (pin "D2") (pinfunction "INT0_D2") (pintype "bidirectional"))
      (node (ref "U$9") (pin "D2") (pinfunction "INT0_D2") (pintype "bidirectional"))
    )
    (net (code "43") (name "/D19-RX1-INT4-3V3") (class "Default")
      (node (ref "IC4") (pin "4") (pinfunction "O_4") (pintype "output"))
      (node (ref "U$12") (pin "12") (pinfunction "12_12") (pintype "passive"))
    )
    (net (code "44") (name "/D20-SDA-INT3") (class "Default")
      (node (ref "IC2") (pin "9") (pinfunction "I_9") (pintype "input"))
      (node (ref "IC3") (pin "44") (pinfunction "(SDA/INT1)PD1_44") (pintype "bidirectional"))
      (node (ref "SDA_PU") (pin "1") (pinfunction "1_1") (pintype "passive"))
      (node (ref "U$11") (pin "2") (pinfunction "2_2") (pintype "passive"))
      (node (ref "U$7") (pin "A4") (pinfunction "SDA_A4") (pintype "bidirectional"))
      (node (ref "U$7") (pin "SDA") (pinfunction "SDA1_SDA") (pintype "bidirectional"))
      (node (ref "U$9") (pin "A4") (pinfunction "SDA_A4") (pintype "bidirectional"))
      (node (ref "U$9") (pin "SDA") (pinfunction "SDA1_SDA") (pintype "bidirectional"))
    )
    (net (code "45") (name "/D20-SDA-INT3-3V3") (class "Default")
      (node (ref "IC2") (pin "10") (pinfunction "O_10") (pintype "output"))
      (node (ref "U$12") (pin "6") (pinfunction "6_6") (pintype "passive"))
    )
    (net (code "46") (name "/D21-SCL-INT2") (class "Default")
      (node (ref "IC2") (pin "11") (pinfunction "I_11") (pintype "input"))
      (node (ref "IC3") (pin "43") (pinfunction "(SCL/INT0)PD0_43") (pintype "bidirectional"))
      (node (ref "SCL_PU") (pin "1") (pinfunction "1_1") (pintype "passive"))
      (node (ref "U$11") (pin "3") (pinfunction "3_3") (pintype "passive"))
      (node (ref "U$7") (pin "A5") (pinfunction "SCL_A5") (pintype "bidirectional"))
      (node (ref "U$7") (pin "SCL") (pinfunction "SCL1_SCL") (pintype "bidirectional"))
      (node (ref "U$9") (pin "A5") (pinfunction "SCL_A5") (pintype "bidirectional"))
      (node (ref "U$9") (pin "SCL") (pinfunction "SCL1_SCL") (pintype "bidirectional"))
    )
    (net (code "47") (name "/D21-SCL-INT2-3V3") (class "Default")
      (node (ref "IC2") (pin "12") (pinfunction "O_12") (pintype "output"))
      (node (ref "U$12") (pin "5") (pinfunction "5_5") (pintype "passive"))
    )
    (net (code "48") (name "/D22") (class "Default")
      (node (ref "IC3") (pin "78") (pinfunction "(AD0)PA0_78") (pintype "bidirectional"))
      (node (ref "JP7") (pin "1") (pinfunction "1_1") (pintype "passive"))
    )
    (net (code "49") (name "/D23") (class "Default")
      (node (ref "IC3") (pin "77") (pinfunction "(AD1)PA1_77") (pintype "bidirectional"))
      (node (ref "JP7") (pin "3") (pinfunction "3_3") (pintype "passive"))
    )
    (net (code "50") (name "/D24") (class "Default")
      (node (ref "IC3") (pin "76") (pinfunction "(AD2)PA2_76") (pintype "bidirectional"))
      (node (ref "JP7") (pin "5") (pinfunction "5_5") (pintype "passive"))
    )
    (net (code "51") (name "/D25") (class "Default")
      (node (ref "IC3") (pin "75") (pinfunction "(AD3)PA3_75") (pintype "bidirectional"))
      (node (ref "JP7") (pin "7") (pinfunction "7_7") (pintype "passive"))
    )
    (net (code "52") (name "/D26") (class "Default")
      (node (ref "IC3") (pin "74") (pinfunction "(AD4)PA4_74") (pintype "bidirectional"))
      (node (ref "JP7") (pin "9") (pinfunction "9_9") (pintype "passive"))
    )
    (net (code "53") (name "/D27") (class "Default")
      (node (ref "IC3") (pin "73") (pinfunction "(AD5)PA5_73") (pintype "bidirectional"))
      (node (ref "JP7") (pin "10") (pinfunction "10_10") (pintype "passive"))
    )
    (net (code "54") (name "/D28") (class "Default")
      (node (ref "IC3") (pin "72") (pinfunction "(AD6)PA6_72") (pintype "bidirectional"))
      (node (ref "JP7") (pin "8") (pinfunction "8_8") (pintype "passive"))
    )
    (net (code "55") (name "/D29") (class "Default")
      (node (ref "IC3") (pin "71") (pinfunction "(AD7)PA7_71") (pintype "bidirectional"))
      (node (ref "JP7") (pin "6") (pinfunction "6_6") (pintype "passive"))
    )
    (net (code "56") (name "/D30") (class "Default")
      (node (ref "IC3") (pin "60") (pinfunction "(A15)PC7_60") (pintype "bidirectional"))
      (node (ref "JP7") (pin "4") (pinfunction "4_4") (pintype "passive"))
    )
    (net (code "57") (name "/D31") (class "Default")
      (node (ref "IC3") (pin "59") (pinfunction "(A14)PC6_59") (pintype "bidirectional"))
    )
    (net (code "58") (name "/D32") (class "Default")
      (node (ref "IC3") (pin "58") (pinfunction "(A13)PC5_58") (pintype "bidirectional"))
    )
    (net (code "59") (name "/D33") (class "Default")
      (node (ref "IC3") (pin "57") (pinfunction "(A12)PC4_57") (pintype "bidirectional"))
      (node (ref "IC4") (pin "7") (pinfunction "I_7") (pintype "input"))
    )
    (net (code "60") (name "/D33-3V3") (class "Default")
      (node (ref "IC4") (pin "6") (pinfunction "O_6") (pintype "output"))
      (node (ref "U$12") (pin "13") (pinfunction "13_13") (pintype "passive"))
    )
    (net (code "61") (name "/D34") (class "Default")
      (node (ref "IC3") (pin "56") (pinfunction "(A11)PC3_56") (pintype "bidirectional"))
      (node (ref "IC4") (pin "9") (pinfunction "I_9") (pintype "input"))
    )
    (net (code "62") (name "/D34-3V3") (class "Default")
      (node (ref "IC4") (pin "10") (pinfunction "O_10") (pintype "output"))
      (node (ref "U$12") (pin "4") (pinfunction "4_4") (pintype "passive"))
    )
    (net (code "63") (name "/D35") (class "Default")
      (node (ref "IC3") (pin "55") (pinfunction "(A10)PC2_55") (pintype "bidirectional"))
      (node (ref "IC4") (pin "11") (pinfunction "I_11") (pintype "input"))
    )
    (net (code "64") (name "/D35-3V3") (class "Default")
      (node (ref "IC4") (pin "12") (pinfunction "O_12") (pintype "output"))
      (node (ref "U$12") (pin "3") (pinfunction "3_3") (pintype "passive"))
    )
    (net (code "65") (name "/D36") (class "Default")
      (node (ref "IC3") (pin "54") (pinfunction "(A9)PC1_54") (pintype "bidirectional"))
      (node (ref "IC4") (pin "14") (pinfunction "I_14") (pintype "input"))
    )
    (net (code "66") (name "/D36-3V3") (class "Default")
      (node (ref "IC4") (pin "15") (pinfunction "O_15") (pintype "output"))
      (node (ref "U$12") (pin "2") (pinfunction "2_2") (pintype "passive"))
    )
    (net (code "67") (name "/D37") (class "Default")
      (node (ref "IC2") (pin "14") (pinfunction "I_14") (pintype "input"))
      (node (ref "IC3") (pin "53") (pinfunction "(A8)PC0_53") (pintype "bidirectional"))
    )
    (net (code "68") (name "/D37-3V3") (class "Default")
      (node (ref "IC2") (pin "15") (pinfunction "O_15") (pintype "output"))
      (node (ref "U$12") (pin "1") (pinfunction "1_1") (pintype "passive"))
    )
    (net (code "69") (name "/D38-SHIELD4") (class "Default")
      (node (ref "IC3") (pin "50") (pinfunction "(T0)PD7_50") (pintype "bidirectional"))
      (node (ref "U$7") (pin "D4") (pinfunction "D4_D4") (pintype "bidirectional"))
    )
    (net (code "70") (name "/D39-SWVCC") (class "Default")
      (node (ref "IC3") (pin "70") (pinfunction "(ALE)PG2_70") (pintype "bidirectional"))
      (node (ref "M0/SW") (pin "5") (pinfunction "ON/OFF_5") (pintype "bidirectional"))
      (node (ref "M1") (pin "5") (pinfunction "ON/OFF_5") (pintype "bidirectional"))
      (node (ref "M2") (pin "5") (pinfunction "ON/OFF_5") (pintype "bidirectional"))
    )
    (net (code "71") (name "/D40-SHIELD0_CS") (class "Default")
      (node (ref "IC3") (pin "52") (pinfunction "(RD)PG1_52") (pintype "bidirectional"))
      (node (ref "U$9") (pin "D10") (pinfunction "CS_D10") (pintype "bidirectional"))
    )
    (net (code "72") (name "/D41-SHIELD1_CS") (class "Default")
      (node (ref "IC3") (pin "51") (pinfunction "(WR)PG0_51") (pintype "bidirectional"))
      (node (ref "U$7") (pin "D10") (pinfunction "CS_D10") (pintype "bidirectional"))
    )
    (net (code "73") (name "/D42-SENSE_3V3_SWITCH") (class "Default")
      (node (ref "IC3") (pin "42") (pinfunction "PL7_42") (pintype "bidirectional"))
      (node (ref "LD0_SENSE") (pin "3") (pinfunction "EN_3") (pintype "bidirectional"))
    )
    (net (code "74") (name "/D43_MANUAL_LOG") (class "Default")
      (node (ref "IC3") (pin "41") (pinfunction "PL6_41") (pintype "bidirectional"))
      (node (ref "MANUAL_LOG") (pin "3") (pinfunction "S_3") (pintype "passive"))
    )
    (net (code "75") (name "/D44") (class "Default")
      (node (ref "IC3") (pin "40") (pinfunction "PL5(OC5C)_40") (pintype "bidirectional"))
      (node (ref "U$11") (pin "15") (pinfunction "15_15") (pintype "passive"))
    )
    (net (code "76") (name "/D45") (class "Default")
      (node (ref "IC3") (pin "39") (pinfunction "PL4(OC5B)_39") (pintype "bidirectional"))
      (node (ref "U$11") (pin "16") (pinfunction "16_16") (pintype "passive"))
    )
    (net (code "77") (name "/D46-SHIELD7") (class "Default")
      (node (ref "IC3") (pin "38") (pinfunction "PL3(OC5A)_38") (pintype "bidirectional"))
      (node (ref "U$7") (pin "D7") (pinfunction "D7_D7") (pintype "bidirectional"))
    )
    (net (code "78") (name "/D47_CS_RTC") (class "Default")
      (node (ref "IC3") (pin "37") (pinfunction "PL2(T5)_37") (pintype "bidirectional"))
      (node (ref "RTC_DS3234") (pin "1") (pinfunction "CS_1") (pintype "bidirectional"))
    )
    (net (code "79") (name "/D48-SD_3V3_SWITCH") (class "Default")
      (node (ref "IC3") (pin "36") (pinfunction "PL1(ICP5)_36") (pintype "bidirectional"))
      (node (ref "LD0_SD") (pin "3") (pinfunction "EN_3") (pintype "bidirectional"))
    )
    (net (code "80") (name "/D49-LED") (class "Default")
      (node (ref "IC3") (pin "35") (pinfunction "PL0(ICP4)_35") (pintype "bidirectional"))
      (node (ref "R_LED") (pin "1") (pinfunction "1_1") (pintype "passive"))
    )
    (net (code "81") (name "/D50-MISO") (class "Default")
      (node (ref "IC2") (pin "3") (pinfunction "I_3") (pintype "input"))
      (node (ref "IC3") (pin "22") (pinfunction "(MISO/PCINT3)PB3_22") (pintype "bidirectional"))
      (node (ref "ISP") (pin "1") (pinfunction "MISO_1") (pintype "input"))
      (node (ref "RTC_DS3234") (pin "19") (pinfunction "DOUT_19") (pintype "bidirectional"))
      (node (ref "SD") (pin "7") (pinfunction "DATA_OUT_7") (pintype "output"))
      (node (ref "U$14") (pin "13") (pinfunction "13_13") (pintype "passive"))
      (node (ref "U$7") (pin "D12") (pinfunction "MISO_D12") (pintype "bidirectional"))
      (node (ref "U$9") (pin "D12") (pinfunction "MISO_D12") (pintype "bidirectional"))
    )
    (net (code "82") (name "/D50-MISO-3V3") (class "Default")
      (node (ref "IC2") (pin "2") (pinfunction "O_2") (pintype "output"))
      (node (ref "U$12") (pin "9") (pinfunction "9_9") (pintype "passive"))
    )
    (net (code "83") (name "/D51-MOSI") (class "Default")
      (node (ref "IC2") (pin "5") (pinfunction "I_5") (pintype "input"))
      (node (ref "IC3") (pin "21") (pinfunction "(MOSI/PCINT2)PB2_21") (pintype "bidirectional"))
      (node (ref "ISP") (pin "4") (pinfunction "MOSI_4") (pintype "output"))
      (node (ref "LSHIFT") (pin "5") (pinfunction "I_5") (pintype "input"))
      (node (ref "RTC_DS3234") (pin "17") (pinfunction "DIN_17") (pintype "bidirectional"))
      (node (ref "U$14") (pin "14") (pinfunction "14_14") (pintype "passive"))
      (node (ref "U$7") (pin "D11") (pinfunction "MOSI_D11") (pintype "bidirectional"))
      (node (ref "U$9") (pin "D11") (pinfunction "MOSI_D11") (pintype "bidirectional"))
    )
    (net (code "84") (name "/D51-MOSI-3V3") (class "Default")
      (node (ref "IC2") (pin "4") (pinfunction "O_4") (pintype "output"))
      (node (ref "U$12") (pin "8") (pinfunction "8_8") (pintype "passive"))
    )
    (net (code "85") (name "/D52-SCLK") (class "Default")
      (node (ref "IC2") (pin "7") (pinfunction "I_7") (pintype "input"))
      (node (ref "IC3") (pin "20") (pinfunction "(SCK/PCINT1)PB1_20") (pintype "bidirectional"))
      (node (ref "ISP") (pin "3") (pinfunction "SCK_3") (pintype "output"))
      (node (ref "LSHIFT") (pin "3") (pinfunction "I_3") (pintype "input"))
      (node (ref "RTC_DS3234") (pin "18") (pinfunction "SCLK_18") (pintype "bidirectional"))
      (node (ref "RTC_DS3234") (pin "20") (pinfunction "SCLK_20") (pintype "bidirectional"))
      (node (ref "U$14") (pin "15") (pinfunction "15_15") (pintype "passive"))
      (node (ref "U$7") (pin "D13") (pinfunction "SCK_D13") (pintype "bidirectional"))
      (node (ref "U$9") (pin "D13") (pinfunction "SCK_D13") (pintype "bidirectional"))
    )
    (net (code "86") (name "/D52-SCLK-3V3") (class "Default")
      (node (ref "IC2") (pin "6") (pinfunction "O_6") (pintype "output"))
      (node (ref "U$12") (pin "7") (pinfunction "7_7") (pintype "passive"))
    )
    (net (code "87") (name "/D53-CS_SD") (class "Default")
      (node (ref "IC3") (pin "19") (pinfunction "(SS/PCINT0)PB0_19") (pintype "bidirectional"))
      (node (ref "LSHIFT") (pin "7") (pinfunction "I_7") (pintype "input"))
    )
    (net (code "88") (name "/DTR") (class "Default")
      (node (ref "C_RESET") (pin "1") (pinfunction "1_1") (pintype "passive"))
      (node (ref "U1") (pin "2") (pinfunction "DTR_2") (pintype "bidirectional"))
    )
    (net (code "89") (name "/RESET") (class "Default")
      (node (ref "C1") (pin "1") (pinfunction "1_1") (pintype "passive"))
      (node (ref "C_RESET") (pin "2") (pinfunction "2_2") (pintype "passive"))
      (node (ref "D3") (pin "A") (pinfunction "A_A") (pintype "passive"))
      (node (ref "IC3") (pin "30") (pinfunction "RESET_30") (pintype "input"))
      (node (ref "ISP") (pin "5") (pinfunction "RST_5") (pintype "output"))
      (node (ref "R_RESET") (pin "1") (pinfunction "1_1") (pintype "passive"))
      (node (ref "S2") (pin "3") (pinfunction "3_3") (pintype "passive"))
      (node (ref "S2") (pin "4") (pinfunction "4_4") (pintype "passive"))
      (node (ref "U$7") (pin "RES") (pinfunction "/RESET_RES") (pintype "bidirectional"))
      (node (ref "U$9") (pin "RES") (pinfunction "/RESET_RES") (pintype "bidirectional"))
    )
    (net (code "90") (name "/SD_CLK") (class "Default")
      (node (ref "LSHIFT") (pin "2") (pinfunction "O_2") (pintype "output"))
      (node (ref "SD") (pin "5") (pinfunction "SCLK_5") (pintype "input"))
    )
    (net (code "91") (name "/SD_CS") (class "Default")
      (node (ref "LSHIFT") (pin "6") (pinfunction "O_6") (pintype "output"))
      (node (ref "SD") (pin "1") (pinfunction "CS_1") (pintype "input"))
    )
    (net (code "92") (name "/SD_DI") (class "Default")
      (node (ref "LSHIFT") (pin "4") (pinfunction "O_4") (pintype "output"))
      (node (ref "SD") (pin "2") (pinfunction "DATA_IN_2") (pintype "input"))
    )
    (net (code "93") (name "/VCC_SW") (class "Default")
      (node (ref "M0/SW") (pin "2") (pinfunction "VOUT,C1_PIN2_2") (pintype "bidirectional"))
      (node (ref "U$11") (pin "10") (pinfunction "10_10") (pintype "passive"))
      (node (ref "U$11") (pin "11") (pinfunction "11_11") (pintype "passive"))
      (node (ref "U$14") (pin "8") (pinfunction "8_8") (pintype "passive"))
    )
    (net (code "94") (name "/VCC_SW_SHIELD1") (class "Default")
      (node (ref "M1") (pin "2") (pinfunction "VOUT,C1_PIN2_2") (pintype "bidirectional"))
      (node (ref "U$9") (pin "5V") (pinfunction "VCC_5V") (pintype "power_in"))
      (node (ref "U$9") (pin "IOREF") (pinfunction "IOREF_IOREF") (pintype "bidirectional"))
      (node (ref "U$9") (pin "VIN") (pinfunction "VIN_VIN") (pintype "power_in"))
    )
    (net (code "95") (name "/VCC_SW_SHIELD2") (class "Default")
      (node (ref "M2") (pin "2") (pinfunction "VOUT,C1_PIN2_2") (pintype "bidirectional"))
      (node (ref "U$7") (pin "5V") (pinfunction "VCC_5V") (pintype "power_in"))
      (node (ref "U$7") (pin "IOREF") (pinfunction "IOREF_IOREF") (pintype "bidirectional"))
      (node (ref "U$7") (pin "VIN") (pinfunction "VIN_VIN") (pintype "power_in"))
    )
    (net (code "96") (name "/XTAL1") (class "Default")
      (node (ref "CX1") (pin "2") (pinfunction "2_2") (pintype "passive"))
      (node (ref "IC3") (pin "34") (pinfunction "XTAL1_34") (pintype "input"))
      (node (ref "U$8") (pin "IO1") (pinfunction "IO1_IO1") (pintype "bidirectional"))
    )
    (net (code "97") (name "/XTAL2") (class "Default")
      (node (ref "CX0") (pin "2") (pinfunction "2_2") (pintype "passive"))
      (node (ref "IC3") (pin "33") (pinfunction "XTAL2_33") (pintype "output"))
      (node (ref "U$8") (pin "IO2") (pinfunction "IO2_IO2") (pintype "bidirectional"))
    )
    (net (code "98") (name "GND") (class "Default")
      (node (ref "C1") (pin "2") (pinfunction "2_2") (pintype "passive"))
      (node (ref "C11") (pin "1") (pinfunction "1_1") (pintype "passive"))
      (node (ref "C3") (pin "2") (pinfunction "2_2") (pintype "passive"))
      (node (ref "C4") (pin "2") (pinfunction "2_2") (pintype "passive"))
      (node (ref "C5") (pin "2") (pinfunction "2_2") (pintype "passive"))
      (node (ref "C6") (pin "2") (pinfunction "2_2") (pintype "passive"))
      (node (ref "CBB") (pin "C") (pinfunction "-_C") (pintype "passive"))
      (node (ref "CLOCK_BATT") (pin "-") (pinfunction "-_-") (pintype "passive"))
      (node (ref "COUT") (pin "2") (pinfunction "2_2") (pintype "passive"))
      (node (ref "CX0") (pin "1") (pinfunction "1_1") (pintype "passive"))
      (node (ref "CX1") (pin "1") (pinfunction "1_1") (pintype "passive"))
      (node (ref "C_LDO_SD") (pin "1") (pinfunction "1_1") (pintype "passive"))
      (node (ref "C_LDO_SENSE") (pin "1") (pinfunction "1_1") (pintype "passive"))
      (node (ref "DECOUP") (pin "2") (pinfunction "2_2") (pintype "passive"))
      (node (ref "H1") (pin "1") (pinfunction "1_1") (pintype "passive"))
      (node (ref "IC1") (pin "2") (pinfunction "GND_2") (pintype "passive"))
      (node (ref "IC1") (pin "3") (pinfunction "CTL_3") (pintype "input"))
      (node (ref "IC2") (pin "8") (pinfunction "VSS_8") (pintype "power_in"))
      (node (ref "IC3") (pin "11") (pinfunction "GND_11") (pintype "power_in"))
      (node (ref "IC3") (pin "32") (pinfunction "GND1_32") (pintype "power_in"))
      (node (ref "IC3") (pin "62") (pinfunction "GND2_62") (pintype "power_in"))
      (node (ref "IC3") (pin "81") (pinfunction "GND3_81") (pintype "power_in"))
      (node (ref "IC3") (pin "99") (pinfunction "AGND_99") (pintype "power_in"))
      (node (ref "IC4") (pin "8") (pinfunction "VSS_8") (pintype "power_in"))
      (node (ref "ISP") (pin "6") (pinfunction "GND_6") (pintype "power_in"))
      (node (ref "J1") (pin "GND") (pinfunction "GND_GND") (pintype "bidirectional"))
      (node (ref "J1") (pin "GNDBREAK") (pinfunction "GNDBREAK_GNDBREAK") (pintype "bidirectional"))
      (node (ref "JP5") (pin "GND") (pinfunction "GND_GND") (pintype "bidirectional"))
      (node (ref "JP7") (pin "2") (pinfunction "2_2") (pintype "passive"))
      (node (ref "LD0_SD") (pin "2") (pinfunction "GND_2") (pintype "bidirectional"))
      (node (ref "LD0_SENSE") (pin "2") (pinfunction "GND_2") (pintype "bidirectional"))
      (node (ref "LED") (pin "K") (pinfunction "C_K") (pintype "passive"))
      (node (ref "LSHIFT") (pin "11") (pinfunction "I_11") (pintype "input"))
      (node (ref "LSHIFT") (pin "14") (pinfunction "I_14") (pintype "input"))
      (node (ref "LSHIFT") (pin "8") (pinfunction "VSS_8") (pintype "power_in"))
      (node (ref "LSHIFT") (pin "9") (pinfunction "I_9") (pintype "input"))
      (node (ref "M0R1") (pin "1") (pinfunction "1_1") (pintype "passive"))
      (node (ref "M1R2") (pin "1") (pinfunction "1_1") (pintype "passive"))
      (node (ref "M2R2") (pin "1") (pinfunction "1_1") (pintype "passive"))
      (node (ref "MANUAL_LOG") (pin "2") (pinfunction "P_2") (pintype "passive"))
      (node (ref "MANUAL_LOG") (pin "4") (pinfunction "P_4") (pintype "passive"))
      (node (ref "RTC_DS3234") (pin "10") (pinfunction "GND_10") (pintype "bidirectional"))
      (node (ref "RTC_DS3234") (pin "11") (pinfunction "GND_11") (pintype "bidirectional"))
      (node (ref "RTC_DS3234") (pin "12") (pinfunction "GND_12") (pintype "bidirectional"))
      (node (ref "RTC_DS3234") (pin "13") (pinfunction "GND_13") (pintype "bidirectional"))
      (node (ref "RTC_DS3234") (pin "14") (pinfunction "GND_14") (pintype "bidirectional"))
      (node (ref "RTC_DS3234") (pin "15") (pinfunction "GND_15") (pintype "bidirectional"))
      (node (ref "RTC_DS3234") (pin "2") (pinfunction "GND_2") (pintype "bidirectional"))
      (node (ref "RTC_DS3234") (pin "7") (pinfunction "GND_7") (pintype "bidirectional"))
      (node (ref "RTC_DS3234") (pin "8") (pinfunction "GND_8") (pintype "bidirectional"))
      (node (ref "RTC_DS3234") (pin "9") (pinfunction "GND_9") (pintype "bidirectional"))
      (node (ref "R_REF_A0") (pin "1") (pinfunction "1_1") (pintype "passive"))
      (node (ref "R_REF_A1") (pin "1") (pinfunction "1_1") (pintype "passive"))
      (node (ref "R_REF_A10") (pin "1") (pinfunction "1_1") (pintype "passive"))
      (node (ref "R_REF_A11") (pin "1") (pinfunction "1_1") (pintype "passive"))
      (node (ref "R_REF_A12") (pin "1") (pinfunction "1_1") (pintype "passive"))
      (node (ref "R_REF_A13") (pin "1") (pinfunction "1_1") (pintype "passive"))
      (node (ref "R_REF_A14") (pin "1") (pinfunction "1_1") (pintype "passive"))
      (node (ref "R_REF_A2") (pin "1") (pinfunction "1_1") (pintype "passive"))
      (node (ref "R_REF_A3") (pin "1") (pinfunction "1_1") (pintype "passive"))
      (node (ref "R_REF_A4") (pin "1") (pinfunction "1_1") (pintype "passive"))
      (node (ref "R_REF_A5") (pin "1") (pinfunction "1_1") (pintype "passive"))
      (node (ref "R_REF_A6") (pin "1") (pinfunction "1_1") (pintype "passive"))
      (node (ref "R_REF_A7") (pin "1") (pinfunction "1_1") (pintype "passive"))
      (node (ref "R_REF_A8") (pin "1") (pinfunction "1_1") (pintype "passive"))
      (node (ref "R_REF_A9") (pin "1") (pinfunction "1_1") (pintype "passive"))
      (node (ref "S2") (pin "1") (pinfunction "1_1") (pintype "passive"))
      (node (ref "S2") (pin "2") (pinfunction "2_2") (pintype "passive"))
      (node (ref "SD") (pin "3") (pinfunction "VSS1_3") (pintype "power_in"))
      (node (ref "SD") (pin "6") (pinfunction "VSS2_6") (pintype "power_in"))
      (node (ref "SD") (pin "GP") (pinfunction "GND_GP") (pintype "power_in"))
      (node (ref "SD") (pin "GP3") (pinfunction "COMMON_SW_GP3") (pintype "passive"))
      (node (ref "U$11") (pin "12") (pinfunction "12_12") (pintype "passive"))
      (node (ref "U$11") (pin "13") (pinfunction "13_13") (pintype "passive"))
      (node (ref "U$11") (pin "14") (pinfunction "14_14") (pintype "passive"))
      (node (ref "U$11") (pin "8") (pinfunction "8_8") (pintype "passive"))
      (node (ref "U$11") (pin "9") (pinfunction "9_9") (pintype "passive"))
      (node (ref "U$12") (pin "10") (pinfunction "10_10") (pintype "passive"))
      (node (ref "U$14") (pin "16") (pinfunction "16_16") (pintype "passive"))
      (node (ref "U$14") (pin "6") (pinfunction "6_6") (pintype "passive"))
      (node (ref "U$14") (pin "7") (pinfunction "7_7") (pintype "passive"))
      (node (ref "U$7") (pin "GND@0") (pinfunction "GND_GND@0") (pintype "power_in"))
      (node (ref "U$7") (pin "GND@1") (pinfunction "GND1_GND@1") (pintype "power_in"))
      (node (ref "U$7") (pin "GND@2") (pinfunction "GND2_GND@2") (pintype "power_in"))
      (node (ref "U$8") (pin "GND") (pinfunction "GND_GND") (pintype "power_in"))
      (node (ref "U$9") (pin "GND@0") (pinfunction "GND_GND@0") (pintype "power_in"))
      (node (ref "U$9") (pin "GND@1") (pinfunction "GND1_GND@1") (pintype "power_in"))
      (node (ref "U$9") (pin "GND@2") (pinfunction "GND2_GND@2") (pintype "power_in"))
      (node (ref "U1") (pin "11") (pinfunction "CTS_11") (pintype "bidirectional"))
      (node (ref "U1") (pin "18") (pinfunction "GND2_18") (pintype "power_in"))
      (node (ref "U1") (pin "21") (pinfunction "GND3_21") (pintype "power_in"))
      (node (ref "U1") (pin "25") (pinfunction "AGND_25") (pintype "power_in"))
      (node (ref "U1") (pin "26") (pinfunction "TEST_26") (pintype "input"))
      (node (ref "U1") (pin "7") (pinfunction "GND1_7") (pintype "power_in"))
      (node (ref "USBD0") (pin "2") (pinfunction "2_2") (pintype "passive"))
      (node (ref "USBD1") (pin "C") (pinfunction "-_C") (pintype "passive"))
      (node (ref "VCC_VDIV_2") (pin "1") (pinfunction "1_1") (pintype "passive"))
    )
    (net (code "99") (name "Net-(IC1-GATE)") (class "Default")
      (node (ref "IC1") (pin "5") (pinfunction "GATE_5") (pintype "output"))
      (node (ref "Q1") (pin "1") (pinfunction "G_1") (pintype "passive"))
    )
    (net (code "100") (name "Net-(IC1-STAT)") (class "Default")
      (node (ref "IC1") (pin "4") (pinfunction "STAT_4") (pintype "open_collector"))
      (node (ref "Q2") (pin "1") (pinfunction "G_1") (pintype "passive"))
      (node (ref "RSTAT") (pin "1") (pinfunction "1_1") (pintype "passive"))
    )
    (net (code "101") (name "Net-(LED-PadA)") (class "Default")
      (node (ref "LED") (pin "A") (pinfunction "A_A") (pintype "passive"))
      (node (ref "R_LED") (pin "2") (pinfunction "2_2") (pintype "passive"))
    )
    (net (code "102") (name "Net-(M0/SW-R1,C1)") (class "Default")
      (node (ref "M0/SW") (pin "6") (pinfunction "R1,C1_6") (pintype "bidirectional"))
      (node (ref "M0R2") (pin "2") (pinfunction "2_2") (pintype "passive"))
      (node (ref "MOC1") (pin "1") (pinfunction "1_1") (pintype "passive"))
    )
    (net (code "103") (name "Net-(M0/SW-R2)") (class "Default")
      (node (ref "M0/SW") (pin "1") (pinfunction "R2_1") (pintype "bidirectional"))
      (node (ref "M0R1") (pin "2") (pinfunction "2_2") (pintype "passive"))
    )
    (net (code "104") (name "Net-(M0/SW-VOUT,C1)") (class "Default")
      (node (ref "M0/SW") (pin "3") (pinfunction "VOUT,C1_3") (pintype "bidirectional"))
      (node (ref "MOC1") (pin "2") (pinfunction "2_2") (pintype "passive"))
    )
    (net (code "105") (name "Net-(M1-R1,C1)") (class "Default")
      (node (ref "M1") (pin "6") (pinfunction "R1,C1_6") (pintype "bidirectional"))
      (node (ref "M1C1") (pin "1") (pinfunction "1_1") (pintype "passive"))
      (node (ref "M1R1") (pin "2") (pinfunction "2_2") (pintype "passive"))
    )
    (net (code "106") (name "Net-(M1-R2)") (class "Default")
      (node (ref "M1") (pin "1") (pinfunction "R2_1") (pintype "bidirectional"))
      (node (ref "M1R2") (pin "2") (pinfunction "2_2") (pintype "passive"))
    )
    (net (code "107") (name "Net-(M1-VOUT,C1)") (class "Default")
      (node (ref "M1") (pin "3") (pinfunction "VOUT,C1_3") (pintype "bidirectional"))
      (node (ref "M1C1") (pin "2") (pinfunction "2_2") (pintype "passive"))
    )
    (net (code "108") (name "Net-(M2-R1,C1)") (class "Default")
      (node (ref "M2") (pin "6") (pinfunction "R1,C1_6") (pintype "bidirectional"))
      (node (ref "M2C1") (pin "1") (pinfunction "1_1") (pintype "passive"))
      (node (ref "M2R1") (pin "2") (pinfunction "2_2") (pintype "passive"))
    )
    (net (code "109") (name "Net-(M2-R2)") (class "Default")
      (node (ref "M2") (pin "1") (pinfunction "R2_1") (pintype "bidirectional"))
      (node (ref "M2R2") (pin "2") (pinfunction "2_2") (pintype "passive"))
    )
    (net (code "110") (name "Net-(M2-VOUT,C1)") (class "Default")
      (node (ref "M2") (pin "3") (pinfunction "VOUT,C1_3") (pintype "bidirectional"))
      (node (ref "M2C1") (pin "2") (pinfunction "2_2") (pintype "passive"))
    )
    (net (code "111") (name "Net-(RTC_DS3234-RST)") (class "Default")
      (node (ref "RTC_DS3234") (pin "6") (pinfunction "RST_6") (pintype "bidirectional"))
      (node (ref "RTC_RST_PU") (pin "1") (pinfunction "1_1") (pintype "passive"))
    )
    (net (code "112") (name "Net-(RX-PadA)") (class "Default")
      (node (ref "RX") (pin "A") (pinfunction "A_A") (pintype "passive"))
      (node (ref "R_RXLED") (pin "2") (pinfunction "2_2") (pintype "passive"))
    )
    (net (code "113") (name "Net-(R_TXLED-Pad2)") (class "Default")
      (node (ref "R_TXLED") (pin "2") (pinfunction "2_2") (pintype "passive"))
      (node (ref "TX") (pin "A") (pinfunction "A_A") (pintype "passive"))
    )
    (net (code "114") (name "Net-(U1-RXLED)") (class "Default")
      (node (ref "RX") (pin "C") (pinfunction "C_C") (pintype "passive"))
      (node (ref "U1") (pin "22") (pinfunction "RXLED_22") (pintype "bidirectional"))
    )
    (net (code "115") (name "Net-(U1-TXLED)") (class "Default")
      (node (ref "TX") (pin "C") (pinfunction "C_C") (pintype "passive"))
      (node (ref "U1") (pin "23") (pinfunction "TXLED_23") (pintype "bidirectional"))
    )
    (net (code "116") (name "Net-(U1-USBDM)") (class "Default")
      (node (ref "JP5") (pin "D-") (pinfunction "D-_D-") (pintype "bidirectional"))
      (node (ref "U1") (pin "16") (pinfunction "USBDM_16") (pintype "bidirectional"))
    )
    (net (code "117") (name "Net-(U1-USBDP)") (class "Default")
      (node (ref "JP5") (pin "D+") (pinfunction "D+_D+") (pintype "bidirectional"))
      (node (ref "U1") (pin "15") (pinfunction "USBDP_15") (pintype "bidirectional"))
    )
    (net (code "118") (name "VCC") (class "Default")
      (node (ref "C11") (pin "2") (pinfunction "2_2") (pintype "passive"))
      (node (ref "COUT") (pin "1") (pinfunction "1_1") (pintype "passive"))
      (node (ref "D3") (pin "C") (pinfunction "C_C") (pintype "passive"))
      (node (ref "DECOUP") (pin "1") (pinfunction "1_1") (pintype "passive"))
      (node (ref "IC1") (pin "6") (pinfunction "SEN_6") (pintype "input"))
      (node (ref "IC3") (pin "10") (pinfunction "VCC_10") (pintype "power_in"))
      (node (ref "IC3") (pin "31") (pinfunction "VCC1_31") (pintype "power_in"))
      (node (ref "IC3") (pin "61") (pinfunction "VCC2_61") (pintype "power_in"))
      (node (ref "IC3") (pin "80") (pinfunction "VCC3_80") (pintype "power_in"))
      (node (ref "ISP") (pin "2") (pinfunction "VCC_2") (pintype "power_in"))
      (node (ref "J1") (pin "PWR") (pinfunction "PWR_PWR") (pintype "bidirectional"))
      (node (ref "LD0_SD") (pin "1") (pinfunction "VIN_1") (pintype "bidirectional"))
      (node (ref "LD0_SENSE") (pin "1") (pinfunction "VIN_1") (pintype "bidirectional"))
      (node (ref "L_LPF") (pin "2") (pinfunction "2_2") (pintype "passive"))
      (node (ref "M0/SW") (pin "4") (pinfunction "VIN,R1_4") (pintype "bidirectional"))
      (node (ref "M0R2") (pin "1") (pinfunction "1_1") (pintype "passive"))
      (node (ref "M1") (pin "4") (pinfunction "VIN,R1_4") (pintype "bidirectional"))
      (node (ref "M1R1") (pin "1") (pinfunction "1_1") (pintype "passive"))
      (node (ref "M2") (pin "4") (pinfunction "VIN,R1_4") (pintype "bidirectional"))
      (node (ref "M2R1") (pin "1") (pinfunction "1_1") (pintype "passive"))
      (node (ref "Q1") (pin "2") (pinfunction "S_2") (pintype "passive"))
      (node (ref "Q2") (pin "2") (pinfunction "S_2") (pintype "passive"))
      (node (ref "RSTAT") (pin "2") (pinfunction "2_2") (pintype "passive"))
      (node (ref "RTC_DS3234") (pin "4") (pinfunction "VCC_4") (pintype "bidirectional"))
      (node (ref "RTC_INT_PU") (pin "2") (pinfunction "2_2") (pintype "passive"))
      (node (ref "RTC_RST_PU") (pin "2") (pinfunction "2_2") (pintype "passive"))
      (node (ref "R_RESET") (pin "2") (pinfunction "2_2") (pintype "passive"))
      (node (ref "SCL_PU") (pin "2") (pinfunction "2_2") (pintype "passive"))
      (node (ref "SDA_PU") (pin "2") (pinfunction "2_2") (pintype "passive"))
      (node (ref "U$11") (pin "6") (pinfunction "6_6") (pintype "passive"))
      (node (ref "U$11") (pin "7") (pinfunction "7_7") (pintype "passive"))
      (node (ref "U$14") (pin "5") (pinfunction "5_5") (pintype "passive"))
      (node (ref "VCC_VDIV_1") (pin "2") (pinfunction "2_2") (pintype "passive"))
    )
    (net (code "119") (name "VDD") (class "Default")
      (node (ref "C_LDO_SD") (pin "2") (pinfunction "2_2") (pintype "passive"))
      (node (ref "LD0_SD") (pin "5") (pinfunction "VOUT_5") (pintype "bidirectional"))
      (node (ref "LSHIFT") (pin "1") (pinfunction "VDD_1") (pintype "power_in"))
      (node (ref "SD") (pin "4") (pinfunction "VDD_4") (pintype "power_in"))
    )
    (net (code "120") (name "VUSB") (class "Default")
      (node (ref "JP5") (pin "VBUS") (pinfunction "VBUS_VBUS") (pintype "bidirectional"))
      (node (ref "Q2") (pin "3") (pinfunction "D_3") (pintype "passive"))
      (node (ref "R_RXLED") (pin "1") (pinfunction "1_1") (pintype "passive"))
      (node (ref "R_TXLED") (pin "1") (pinfunction "1_1") (pintype "passive"))
      (node (ref "U1") (pin "20") (pinfunction "VCC_20") (pintype "power_in"))
      (node (ref "U1") (pin "4") (pinfunction "VCCIO_4") (pintype "power_in"))
      (node (ref "USBD0") (pin "1") (pinfunction "1_1") (pintype "passive"))
      (node (ref "USBD1") (pin "A") (pinfunction "+_A") (pintype "passive"))
    )
    (net (code "121") (name "unconnected-(CLOCK_BATT-+1-Pad+$2)") (class "Default")
      (node (ref "CLOCK_BATT") (pin "+$2") (pinfunction "+1_+$2") (pintype "passive"))
    )
    (net (code "122") (name "unconnected-(IC3-(CLKO{slash}ICP3{slash}INT7)PE7-Pad9)") (class "Default")
      (node (ref "IC3") (pin "9") (pinfunction "(CLKO/ICP3/INT7)PE7_9") (pintype "bidirectional"))
    )
    (net (code "123") (name "unconnected-(IC3-(ICP1)PD4-Pad47)") (class "Default")
      (node (ref "IC3") (pin "47") (pinfunction "(ICP1)PD4_47") (pintype "bidirectional"))
    )
    (net (code "124") (name "unconnected-(IC3-(T1)PD6-Pad49)") (class "Default")
      (node (ref "IC3") (pin "49") (pinfunction "(T1)PD6_49") (pintype "bidirectional"))
    )
    (net (code "125") (name "unconnected-(IC3-(T3{slash}INT6)PE6-Pad8)") (class "Default")
      (node (ref "IC3") (pin "8") (pinfunction "(T3/INT6)PE6_8") (pintype "bidirectional"))
    )
    (net (code "126") (name "unconnected-(IC3-(TOSC1)PG4-Pad29)") (class "Default")
      (node (ref "IC3") (pin "29") (pinfunction "(TOSC1)PG4_29") (pintype "bidirectional"))
    )
    (net (code "127") (name "unconnected-(IC3-(TOSC2)PG3-Pad28)") (class "Default")
      (node (ref "IC3") (pin "28") (pinfunction "(TOSC2)PG3_28") (pintype "bidirectional"))
    )
    (net (code "128") (name "unconnected-(IC3-(XCK0{slash}AIN0)PE2-Pad4)") (class "Default")
      (node (ref "IC3") (pin "4") (pinfunction "(XCK0/AIN0)PE2_4") (pintype "bidirectional"))
    )
    (net (code "129") (name "unconnected-(IC3-(XCK1)PD5-Pad48)") (class "Default")
      (node (ref "IC3") (pin "48") (pinfunction "(XCK1)PD5_48") (pintype "bidirectional"))
    )
    (net (code "130") (name "unconnected-(IC3-PH2(XCK2)-Pad14)") (class "Default")
      (node (ref "IC3") (pin "14") (pinfunction "PH2(XCK2)_14") (pintype "bidirectional"))
    )
    (net (code "131") (name "unconnected-(IC3-PH7(T4)-Pad27)") (class "Default")
      (node (ref "IC3") (pin "27") (pinfunction "PH7(T4)_27") (pintype "bidirectional"))
    )
    (net (code "132") (name "unconnected-(IC3-PJ2(XCK3{slash}PCINT11)-Pad65)") (class "Default")
      (node (ref "IC3") (pin "65") (pinfunction "PJ2(XCK3/PCINT11)_65") (pintype "bidirectional"))
    )
    (net (code "133") (name "unconnected-(IC3-PJ3(PCINT12)-Pad66)") (class "Default")
      (node (ref "IC3") (pin "66") (pinfunction "PJ3(PCINT12)_66") (pintype "bidirectional"))
    )
    (net (code "134") (name "unconnected-(IC3-PJ4(PCINT13)-Pad67)") (class "Default")
      (node (ref "IC3") (pin "67") (pinfunction "PJ4(PCINT13)_67") (pintype "bidirectional"))
    )
    (net (code "135") (name "unconnected-(IC3-PJ5(PCINT14)-Pad68)") (class "Default")
      (node (ref "IC3") (pin "68") (pinfunction "PJ5(PCINT14)_68") (pintype "bidirectional"))
    )
    (net (code "136") (name "unconnected-(IC3-PJ6(PCINT15)-Pad69)") (class "Default")
      (node (ref "IC3") (pin "69") (pinfunction "PJ6(PCINT15)_69") (pintype "bidirectional"))
    )
    (net (code "137") (name "unconnected-(IC3-PJ7-Pad79)") (class "Default")
      (node (ref "IC3") (pin "79") (pinfunction "PJ7_79") (pintype "bidirectional"))
    )
    (net (code "138") (name "unconnected-(LD0_SD-BYP-Pad4)") (class "Default")
      (node (ref "LD0_SD") (pin "4") (pinfunction "BYP_4") (pintype "bidirectional"))
    )
    (net (code "139") (name "unconnected-(LD0_SENSE-BYP-Pad4)") (class "Default")
      (node (ref "LD0_SENSE") (pin "4") (pinfunction "BYP_4") (pintype "bidirectional"))
    )
    (net (code "140") (name "unconnected-(LSHIFTD-O-Pad10)") (class "Default")
      (node (ref "LSHIFT") (pin "10") (pinfunction "O_10") (pintype "output"))
    )
    (net (code "141") (name "unconnected-(LSHIFTE-O-Pad12)") (class "Default")
      (node (ref "LSHIFT") (pin "12") (pinfunction "O_12") (pintype "output"))
    )
    (net (code "142") (name "unconnected-(LSHIFTF-O-Pad15)") (class "Default")
      (node (ref "LSHIFT") (pin "15") (pinfunction "O_15") (pintype "output"))
    )
    (net (code "143") (name "unconnected-(RTC_DS3234-32KHZ-Pad3)") (class "Default")
      (node (ref "RTC_DS3234") (pin "3") (pinfunction "32KHZ_3") (pintype "bidirectional"))
    )
    (net (code "144") (name "unconnected-(SD-DAT1-Pad8)") (class "Default")
      (node (ref "SD") (pin "8") (pinfunction "DAT1_8") (pintype "bidirectional"))
    )
    (net (code "145") (name "unconnected-(SD-DAT2-Pad9)") (class "Default")
      (node (ref "SD") (pin "9") (pinfunction "DAT2_9") (pintype "bidirectional"))
    )
    (net (code "146") (name "unconnected-(SD-WRITE_PROTECT-PadWP)") (class "Default")
      (node (ref "SD") (pin "WP") (pinfunction "WRITE_PROTECT_WP") (pintype "passive"))
    )
    (net (code "147") (name "unconnected-(U$7-PadNC)") (class "Default")
      (node (ref "U$7") (pin "NC") (pinfunction "NC_NC") (pintype "bidirectional"))
    )
    (net (code "148") (name "unconnected-(U$9-PadNC)") (class "Default")
      (node (ref "U$9") (pin "NC") (pinfunction "NC_NC") (pintype "bidirectional"))
    )
    (net (code "149") (name "unconnected-(U1-3V3OUT-Pad17)") (class "Default")
      (node (ref "U1") (pin "17") (pinfunction "3V3OUT_17") (pintype "output"))
    )
    (net (code "150") (name "unconnected-(U1-RTS-Pad3)") (class "Default")
      (node (ref "U1") (pin "3") (pinfunction "RTS_3") (pintype "bidirectional"))
    )
  )
)
